# LED_SCHEMATIC.net
KiCad netlist of a schematic drawn in EasyEDA
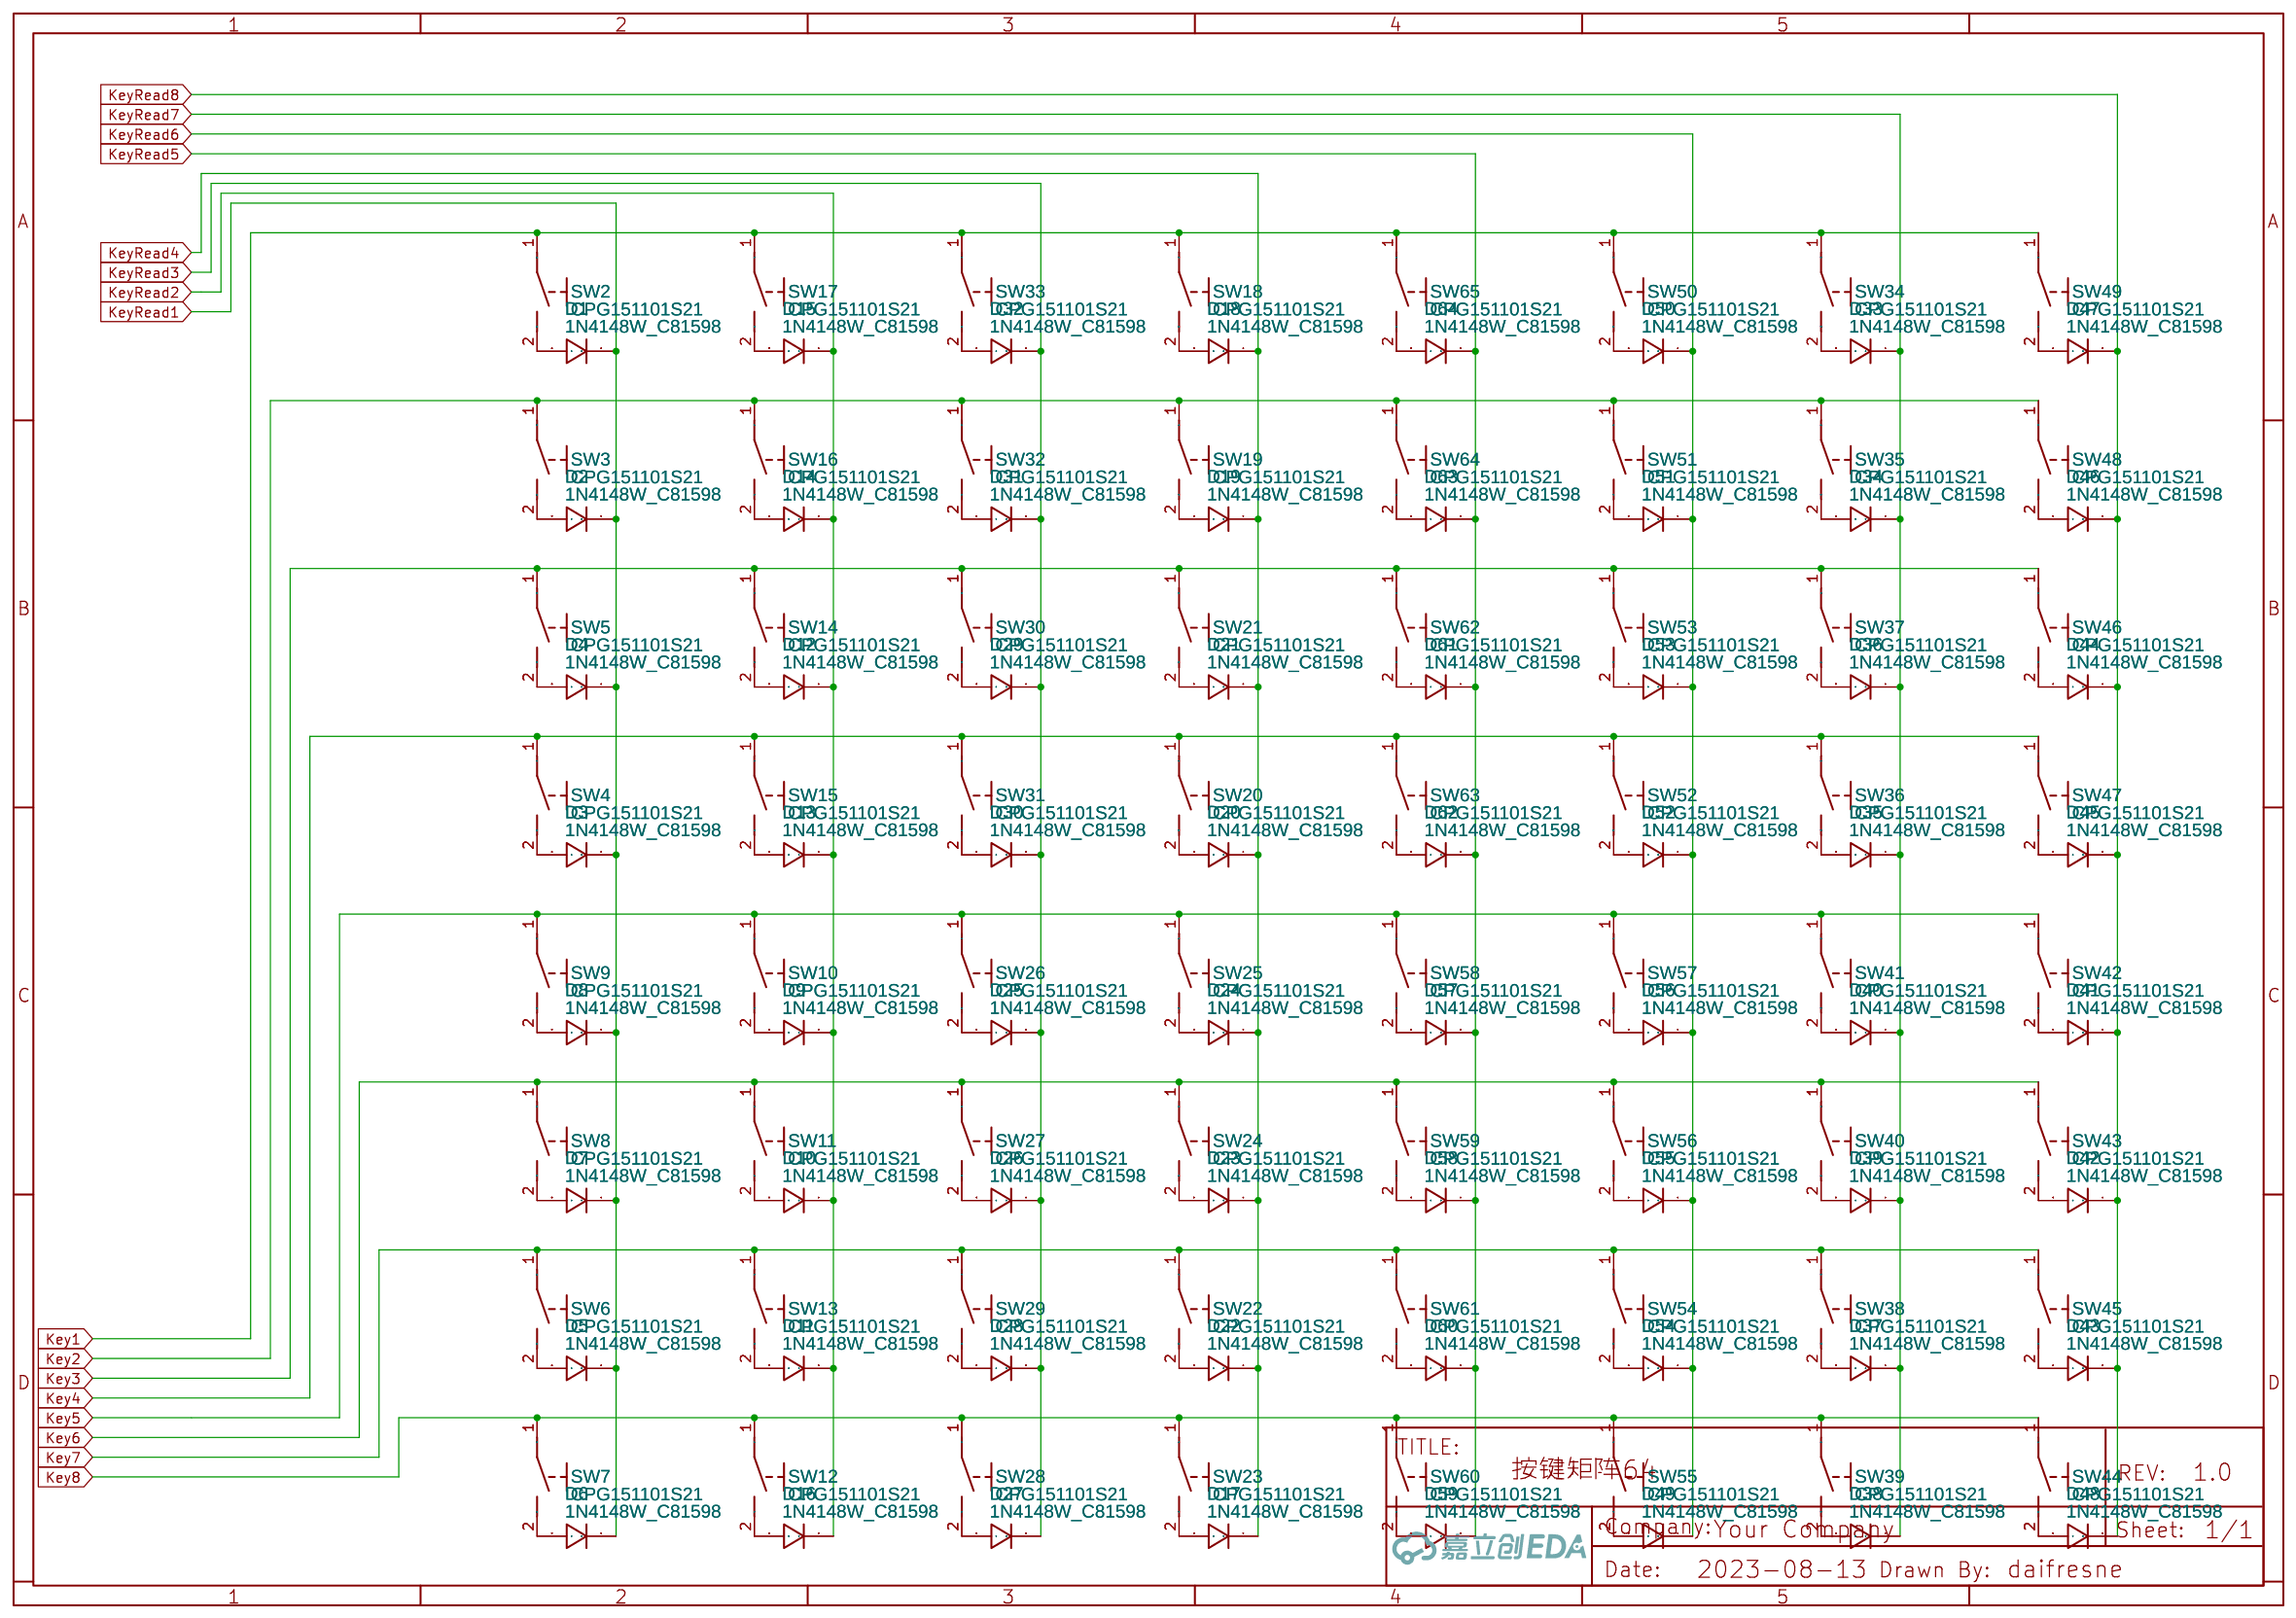
[diagram p0: 按键矩阵64]
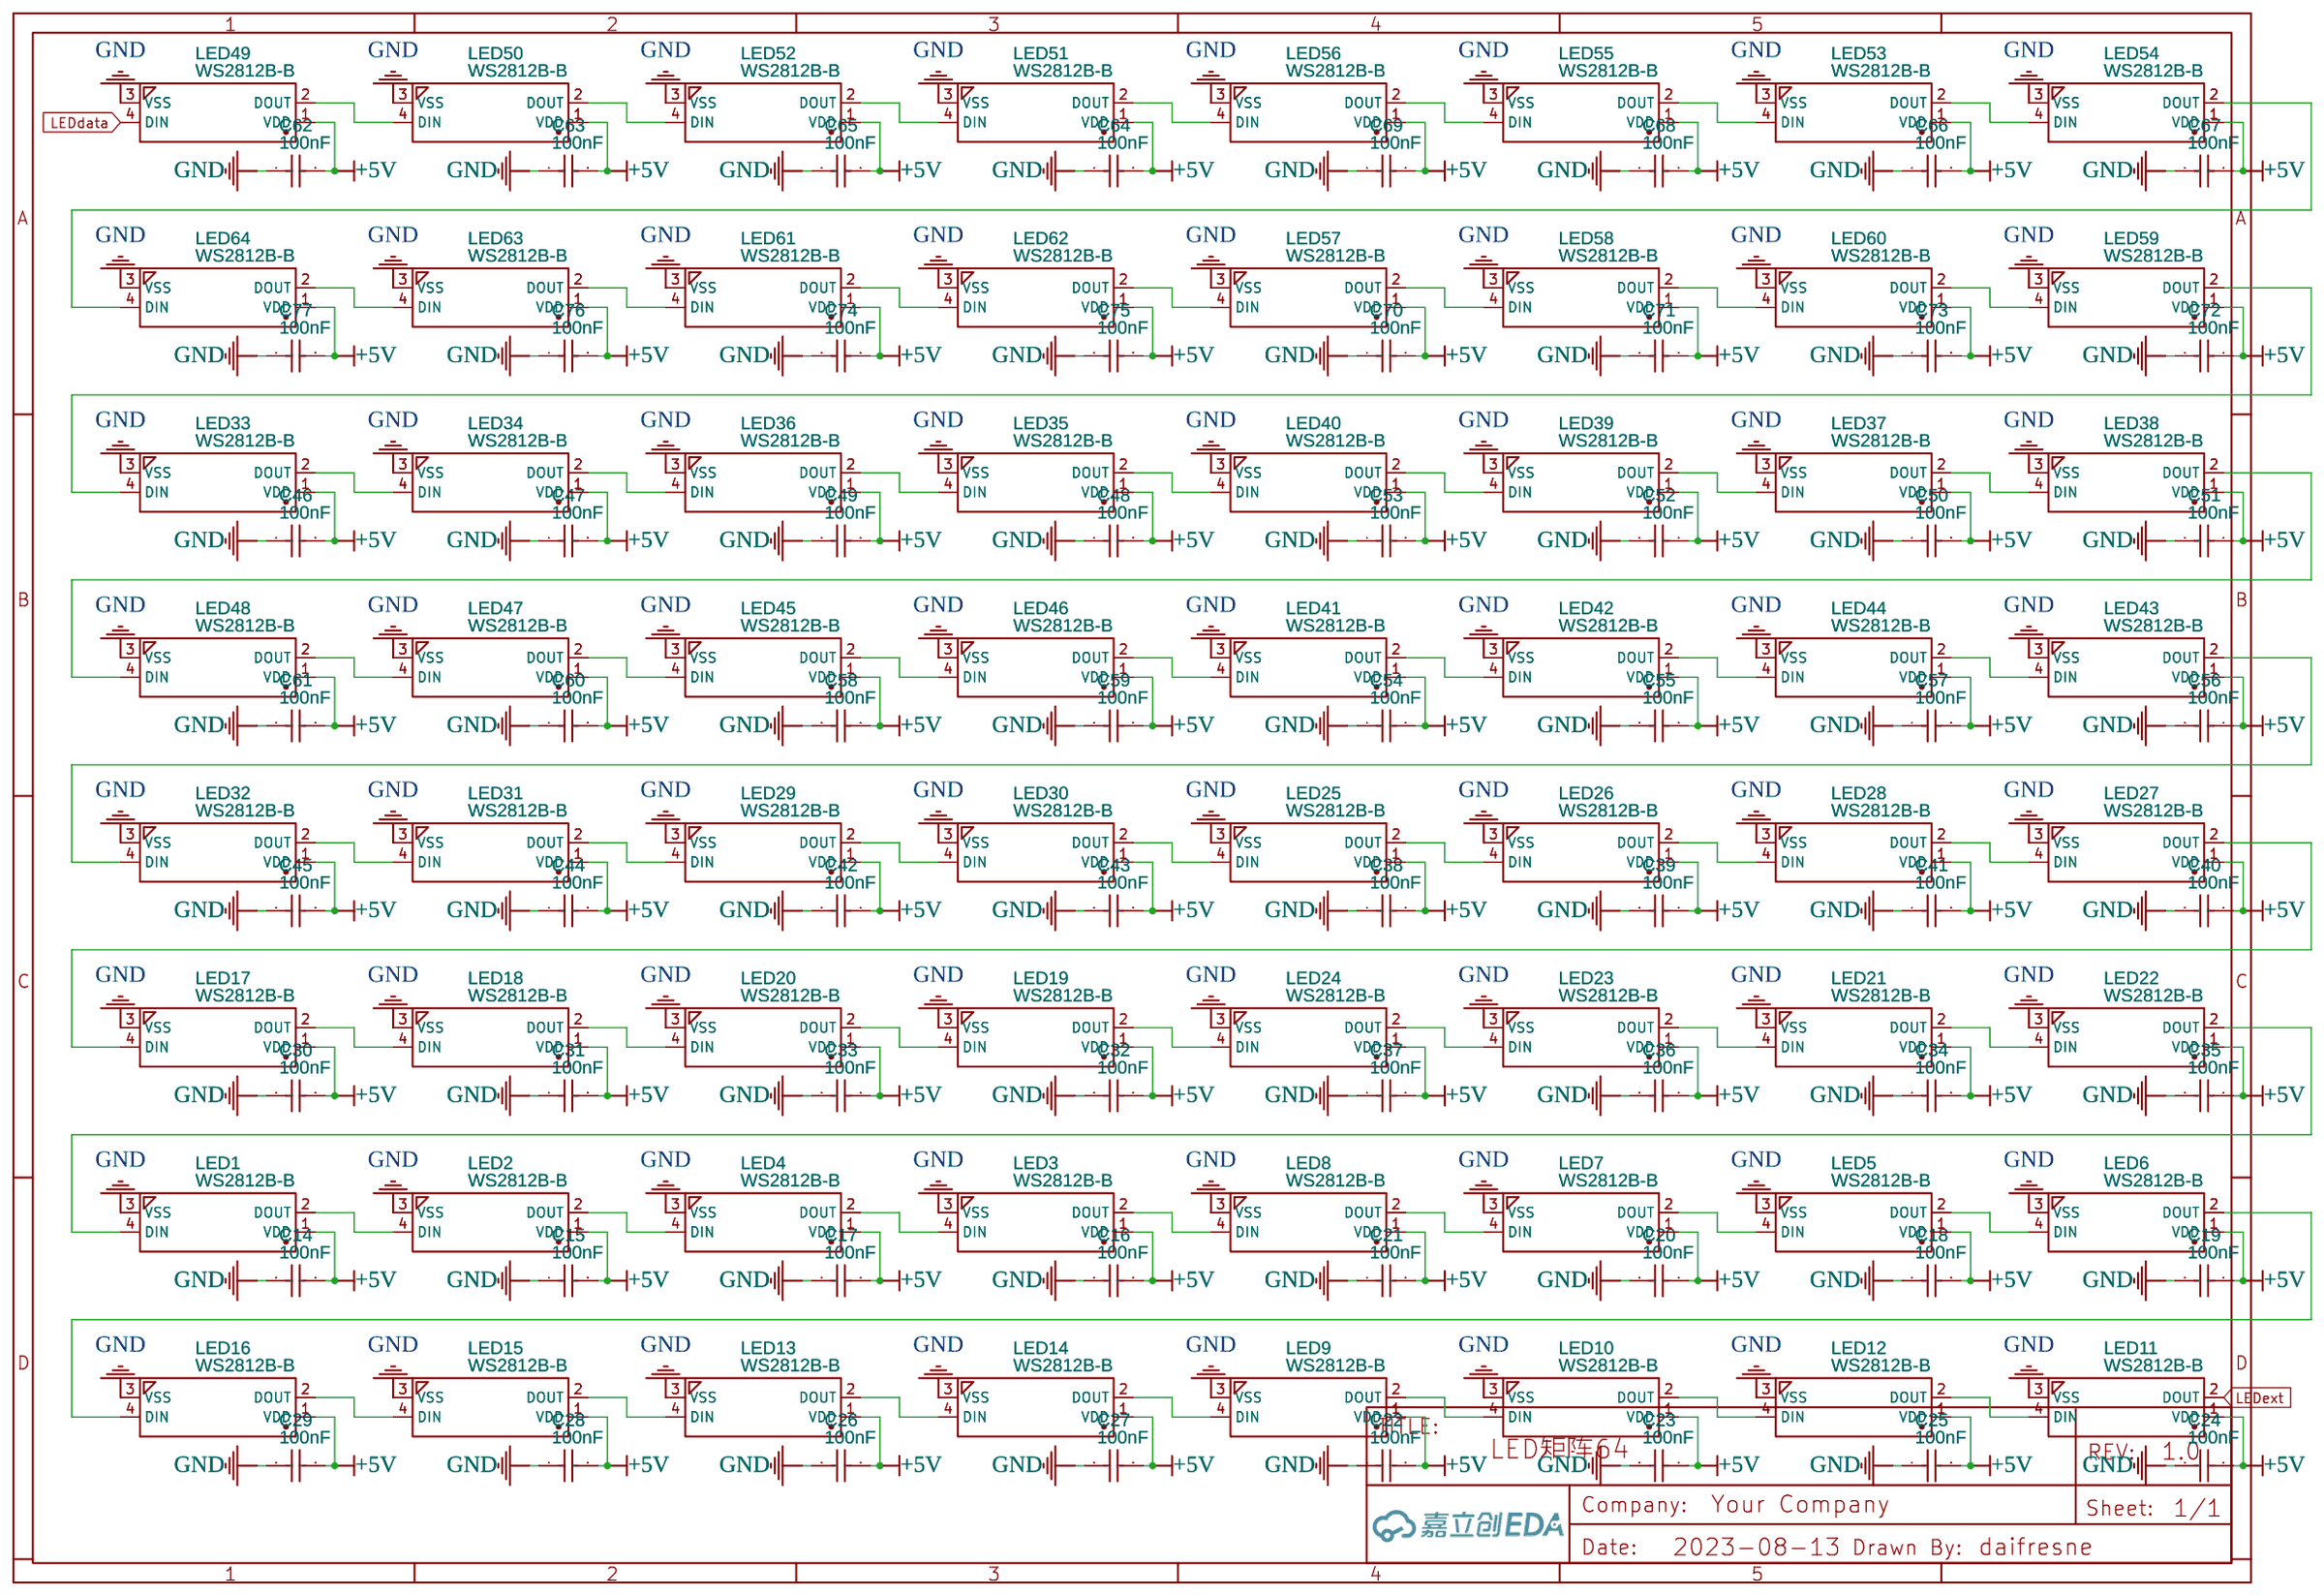
[diagram p1: LED矩阵64]

(export (version "E")
  (design (tool "Eeschema 10.0.6"))
  (components
    (comp (ref "D1")
      (value "1N4148W_C81598")
      (fields (field (name "Manufacturer") "ST(先科)"))
      (libsource (lib "") (part "1N4148W_C81598"))
    )
    (comp (ref "D2")
      (value "1N4148W_C81598")
      (fields (field (name "Manufacturer") "ST(先科)"))
      (libsource (lib "") (part "1N4148W_C81598"))
    )
    (comp (ref "D3")
      (value "1N4148W_C81598")
      (fields (field (name "Manufacturer") "ST(先科)"))
      (libsource (lib "") (part "1N4148W_C81598"))
    )
    (comp (ref "D4")
      (value "1N4148W_C81598")
      (fields (field (name "Manufacturer") "ST(先科)"))
      (libsource (lib "") (part "1N4148W_C81598"))
    )
    (comp (ref "D5")
      (value "1N4148W_C81598")
      (fields (field (name "Manufacturer") "ST(先科)"))
      (libsource (lib "") (part "1N4148W_C81598"))
    )
    (comp (ref "D6")
      (value "1N4148W_C81598")
      (fields (field (name "Manufacturer") "ST(先科)"))
      (libsource (lib "") (part "1N4148W_C81598"))
    )
    (comp (ref "D7")
      (value "1N4148W_C81598")
      (fields (field (name "Manufacturer") "ST(先科)"))
      (libsource (lib "") (part "1N4148W_C81598"))
    )
    (comp (ref "D8")
      (value "1N4148W_C81598")
      (fields (field (name "Manufacturer") "ST(先科)"))
      (libsource (lib "") (part "1N4148W_C81598"))
    )
    (comp (ref "D9")
      (value "1N4148W_C81598")
      (fields (field (name "Manufacturer") "ST(先科)"))
      (libsource (lib "") (part "1N4148W_C81598"))
    )
    (comp (ref "D10")
      (value "1N4148W_C81598")
      (fields (field (name "Manufacturer") "ST(先科)"))
      (libsource (lib "") (part "1N4148W_C81598"))
    )
    (comp (ref "D11")
      (value "1N4148W_C81598")
      (fields (field (name "Manufacturer") "ST(先科)"))
      (libsource (lib "") (part "1N4148W_C81598"))
    )
    (comp (ref "D12")
      (value "1N4148W_C81598")
      (fields (field (name "Manufacturer") "ST(先科)"))
      (libsource (lib "") (part "1N4148W_C81598"))
    )
    (comp (ref "D13")
      (value "1N4148W_C81598")
      (fields (field (name "Manufacturer") "ST(先科)"))
      (libsource (lib "") (part "1N4148W_C81598"))
    )
    (comp (ref "D14")
      (value "1N4148W_C81598")
      (fields (field (name "Manufacturer") "ST(先科)"))
      (libsource (lib "") (part "1N4148W_C81598"))
    )
    (comp (ref "D15")
      (value "1N4148W_C81598")
      (fields (field (name "Manufacturer") "ST(先科)"))
      (libsource (lib "") (part "1N4148W_C81598"))
    )
    (comp (ref "D16")
      (value "1N4148W_C81598")
      (fields (field (name "Manufacturer") "ST(先科)"))
      (libsource (lib "") (part "1N4148W_C81598"))
    )
    (comp (ref "D17")
      (value "1N4148W_C81598")
      (fields (field (name "Manufacturer") "ST(先科)"))
      (libsource (lib "") (part "1N4148W_C81598"))
    )
    (comp (ref "D18")
      (value "1N4148W_C81598")
      (fields (field (name "Manufacturer") "ST(先科)"))
      (libsource (lib "") (part "1N4148W_C81598"))
    )
    (comp (ref "D19")
      (value "1N4148W_C81598")
      (fields (field (name "Manufacturer") "ST(先科)"))
      (libsource (lib "") (part "1N4148W_C81598"))
    )
    (comp (ref "D20")
      (value "1N4148W_C81598")
      (fields (field (name "Manufacturer") "ST(先科)"))
      (libsource (lib "") (part "1N4148W_C81598"))
    )
    (comp (ref "D21")
      (value "1N4148W_C81598")
      (fields (field (name "Manufacturer") "ST(先科)"))
      (libsource (lib "") (part "1N4148W_C81598"))
    )
    (comp (ref "D22")
      (value "1N4148W_C81598")
      (fields (field (name "Manufacturer") "ST(先科)"))
      (libsource (lib "") (part "1N4148W_C81598"))
    )
    (comp (ref "D23")
      (value "1N4148W_C81598")
      (fields (field (name "Manufacturer") "ST(先科)"))
      (libsource (lib "") (part "1N4148W_C81598"))
    )
    (comp (ref "D24")
      (value "1N4148W_C81598")
      (fields (field (name "Manufacturer") "ST(先科)"))
      (libsource (lib "") (part "1N4148W_C81598"))
    )
    (comp (ref "D25")
      (value "1N4148W_C81598")
      (fields (field (name "Manufacturer") "ST(先科)"))
      (libsource (lib "") (part "1N4148W_C81598"))
    )
    (comp (ref "D26")
      (value "1N4148W_C81598")
      (fields (field (name "Manufacturer") "ST(先科)"))
      (libsource (lib "") (part "1N4148W_C81598"))
    )
    (comp (ref "D27")
      (value "1N4148W_C81598")
      (fields (field (name "Manufacturer") "ST(先科)"))
      (libsource (lib "") (part "1N4148W_C81598"))
    )
    (comp (ref "D28")
      (value "1N4148W_C81598")
      (fields (field (name "Manufacturer") "ST(先科)"))
      (libsource (lib "") (part "1N4148W_C81598"))
    )
    (comp (ref "D29")
      (value "1N4148W_C81598")
      (fields (field (name "Manufacturer") "ST(先科)"))
      (libsource (lib "") (part "1N4148W_C81598"))
    )
    (comp (ref "D30")
      (value "1N4148W_C81598")
      (fields (field (name "Manufacturer") "ST(先科)"))
      (libsource (lib "") (part "1N4148W_C81598"))
    )
    (comp (ref "D31")
      (value "1N4148W_C81598")
      (fields (field (name "Manufacturer") "ST(先科)"))
      (libsource (lib "") (part "1N4148W_C81598"))
    )
    (comp (ref "D32")
      (value "1N4148W_C81598")
      (fields (field (name "Manufacturer") "ST(先科)"))
      (libsource (lib "") (part "1N4148W_C81598"))
    )
    (comp (ref "D33")
      (value "1N4148W_C81598")
      (fields (field (name "Manufacturer") "ST(先科)"))
      (libsource (lib "") (part "1N4148W_C81598"))
    )
    (comp (ref "D34")
      (value "1N4148W_C81598")
      (fields (field (name "Manufacturer") "ST(先科)"))
      (libsource (lib "") (part "1N4148W_C81598"))
    )
    (comp (ref "D35")
      (value "1N4148W_C81598")
      (fields (field (name "Manufacturer") "ST(先科)"))
      (libsource (lib "") (part "1N4148W_C81598"))
    )
    (comp (ref "D36")
      (value "1N4148W_C81598")
      (fields (field (name "Manufacturer") "ST(先科)"))
      (libsource (lib "") (part "1N4148W_C81598"))
    )
    (comp (ref "D37")
      (value "1N4148W_C81598")
      (fields (field (name "Manufacturer") "ST(先科)"))
      (libsource (lib "") (part "1N4148W_C81598"))
    )
    (comp (ref "D38")
      (value "1N4148W_C81598")
      (fields (field (name "Manufacturer") "ST(先科)"))
      (libsource (lib "") (part "1N4148W_C81598"))
    )
    (comp (ref "D39")
      (value "1N4148W_C81598")
      (fields (field (name "Manufacturer") "ST(先科)"))
      (libsource (lib "") (part "1N4148W_C81598"))
    )
    (comp (ref "D40")
      (value "1N4148W_C81598")
      (fields (field (name "Manufacturer") "ST(先科)"))
      (libsource (lib "") (part "1N4148W_C81598"))
    )
    (comp (ref "D41")
      (value "1N4148W_C81598")
      (fields (field (name "Manufacturer") "ST(先科)"))
      (libsource (lib "") (part "1N4148W_C81598"))
    )
    (comp (ref "D42")
      (value "1N4148W_C81598")
      (fields (field (name "Manufacturer") "ST(先科)"))
      (libsource (lib "") (part "1N4148W_C81598"))
    )
    (comp (ref "D43")
      (value "1N4148W_C81598")
      (fields (field (name "Manufacturer") "ST(先科)"))
      (libsource (lib "") (part "1N4148W_C81598"))
    )
    (comp (ref "D44")
      (value "1N4148W_C81598")
      (fields (field (name "Manufacturer") "ST(先科)"))
      (libsource (lib "") (part "1N4148W_C81598"))
    )
    (comp (ref "D45")
      (value "1N4148W_C81598")
      (fields (field (name "Manufacturer") "ST(先科)"))
      (libsource (lib "") (part "1N4148W_C81598"))
    )
    (comp (ref "D46")
      (value "1N4148W_C81598")
      (fields (field (name "Manufacturer") "ST(先科)"))
      (libsource (lib "") (part "1N4148W_C81598"))
    )
    (comp (ref "D47")
      (value "1N4148W_C81598")
      (fields (field (name "Manufacturer") "ST(先科)"))
      (libsource (lib "") (part "1N4148W_C81598"))
    )
    (comp (ref "D48")
      (value "1N4148W_C81598")
      (fields (field (name "Manufacturer") "ST(先科)"))
      (libsource (lib "") (part "1N4148W_C81598"))
    )
    (comp (ref "D49")
      (value "1N4148W_C81598")
      (fields (field (name "Manufacturer") "ST(先科)"))
      (libsource (lib "") (part "1N4148W_C81598"))
    )
    (comp (ref "D50")
      (value "1N4148W_C81598")
      (fields (field (name "Manufacturer") "ST(先科)"))
      (libsource (lib "") (part "1N4148W_C81598"))
    )
    (comp (ref "D51")
      (value "1N4148W_C81598")
      (fields (field (name "Manufacturer") "ST(先科)"))
      (libsource (lib "") (part "1N4148W_C81598"))
    )
    (comp (ref "D52")
      (value "1N4148W_C81598")
      (fields (field (name "Manufacturer") "ST(先科)"))
      (libsource (lib "") (part "1N4148W_C81598"))
    )
    (comp (ref "D53")
      (value "1N4148W_C81598")
      (fields (field (name "Manufacturer") "ST(先科)"))
      (libsource (lib "") (part "1N4148W_C81598"))
    )
    (comp (ref "D54")
      (value "1N4148W_C81598")
      (fields (field (name "Manufacturer") "ST(先科)"))
      (libsource (lib "") (part "1N4148W_C81598"))
    )
    (comp (ref "D55")
      (value "1N4148W_C81598")
      (fields (field (name "Manufacturer") "ST(先科)"))
      (libsource (lib "") (part "1N4148W_C81598"))
    )
    (comp (ref "D56")
      (value "1N4148W_C81598")
      (fields (field (name "Manufacturer") "ST(先科)"))
      (libsource (lib "") (part "1N4148W_C81598"))
    )
    (comp (ref "D57")
      (value "1N4148W_C81598")
      (fields (field (name "Manufacturer") "ST(先科)"))
      (libsource (lib "") (part "1N4148W_C81598"))
    )
    (comp (ref "D58")
      (value "1N4148W_C81598")
      (fields (field (name "Manufacturer") "ST(先科)"))
      (libsource (lib "") (part "1N4148W_C81598"))
    )
    (comp (ref "D59")
      (value "1N4148W_C81598")
      (fields (field (name "Manufacturer") "ST(先科)"))
      (libsource (lib "") (part "1N4148W_C81598"))
    )
    (comp (ref "D60")
      (value "1N4148W_C81598")
      (fields (field (name "Manufacturer") "ST(先科)"))
      (libsource (lib "") (part "1N4148W_C81598"))
    )
    (comp (ref "D61")
      (value "1N4148W_C81598")
      (fields (field (name "Manufacturer") "ST(先科)"))
      (libsource (lib "") (part "1N4148W_C81598"))
    )
    (comp (ref "D62")
      (value "1N4148W_C81598")
      (fields (field (name "Manufacturer") "ST(先科)"))
      (libsource (lib "") (part "1N4148W_C81598"))
    )
    (comp (ref "D63")
      (value "1N4148W_C81598")
      (fields (field (name "Manufacturer") "ST(先科)"))
      (libsource (lib "") (part "1N4148W_C81598"))
    )
    (comp (ref "D64")
      (value "1N4148W_C81598")
      (fields (field (name "Manufacturer") "ST(先科)"))
      (libsource (lib "") (part "1N4148W_C81598"))
    )
    (comp (ref "SW2")
      (value "CPG151101S21")
      (fields (field (name "Manufacturer") "Kailh(凯华)"))
      (libsource (lib "") (part "CPG151101S21"))
    )
    (comp (ref "SW3")
      (value "CPG151101S21")
      (fields (field (name "Manufacturer") "Kailh(凯华)"))
      (libsource (lib "") (part "CPG151101S21"))
    )
    (comp (ref "SW4")
      (value "CPG151101S21")
      (fields (field (name "Manufacturer") "Kailh(凯华)"))
      (libsource (lib "") (part "CPG151101S21"))
    )
    (comp (ref "SW5")
      (value "CPG151101S21")
      (fields (field (name "Manufacturer") "Kailh(凯华)"))
      (libsource (lib "") (part "CPG151101S21"))
    )
    (comp (ref "SW6")
      (value "CPG151101S21")
      (fields (field (name "Manufacturer") "Kailh(凯华)"))
      (libsource (lib "") (part "CPG151101S21"))
    )
    (comp (ref "SW7")
      (value "CPG151101S21")
      (fields (field (name "Manufacturer") "Kailh(凯华)"))
      (libsource (lib "") (part "CPG151101S21"))
    )
    (comp (ref "SW8")
      (value "CPG151101S21")
      (fields (field (name "Manufacturer") "Kailh(凯华)"))
      (libsource (lib "") (part "CPG151101S21"))
    )
    (comp (ref "SW9")
      (value "CPG151101S21")
      (fields (field (name "Manufacturer") "Kailh(凯华)"))
      (libsource (lib "") (part "CPG151101S21"))
    )
    (comp (ref "SW10")
      (value "CPG151101S21")
      (fields (field (name "Manufacturer") "Kailh(凯华)"))
      (libsource (lib "") (part "CPG151101S21"))
    )
    (comp (ref "SW11")
      (value "CPG151101S21")
      (fields (field (name "Manufacturer") "Kailh(凯华)"))
      (libsource (lib "") (part "CPG151101S21"))
    )
    (comp (ref "SW12")
      (value "CPG151101S21")
      (fields (field (name "Manufacturer") "Kailh(凯华)"))
      (libsource (lib "") (part "CPG151101S21"))
    )
    (comp (ref "SW13")
      (value "CPG151101S21")
      (fields (field (name "Manufacturer") "Kailh(凯华)"))
      (libsource (lib "") (part "CPG151101S21"))
    )
    (comp (ref "SW14")
      (value "CPG151101S21")
      (fields (field (name "Manufacturer") "Kailh(凯华)"))
      (libsource (lib "") (part "CPG151101S21"))
    )
    (comp (ref "SW15")
      (value "CPG151101S21")
      (fields (field (name "Manufacturer") "Kailh(凯华)"))
      (libsource (lib "") (part "CPG151101S21"))
    )
    (comp (ref "SW16")
      (value "CPG151101S21")
      (fields (field (name "Manufacturer") "Kailh(凯华)"))
      (libsource (lib "") (part "CPG151101S21"))
    )
    (comp (ref "SW17")
      (value "CPG151101S21")
      (fields (field (name "Manufacturer") "Kailh(凯华)"))
      (libsource (lib "") (part "CPG151101S21"))
    )
    (comp (ref "SW18")
      (value "CPG151101S21")
      (fields (field (name "Manufacturer") "Kailh(凯华)"))
      (libsource (lib "") (part "CPG151101S21"))
    )
    (comp (ref "SW19")
      (value "CPG151101S21")
      (fields (field (name "Manufacturer") "Kailh(凯华)"))
      (libsource (lib "") (part "CPG151101S21"))
    )
    (comp (ref "SW20")
      (value "CPG151101S21")
      (fields (field (name "Manufacturer") "Kailh(凯华)"))
      (libsource (lib "") (part "CPG151101S21"))
    )
    (comp (ref "SW21")
      (value "CPG151101S21")
      (fields (field (name "Manufacturer") "Kailh(凯华)"))
      (libsource (lib "") (part "CPG151101S21"))
    )
    (comp (ref "SW22")
      (value "CPG151101S21")
      (fields (field (name "Manufacturer") "Kailh(凯华)"))
      (libsource (lib "") (part "CPG151101S21"))
    )
    (comp (ref "SW23")
      (value "CPG151101S21")
      (fields (field (name "Manufacturer") "Kailh(凯华)"))
      (libsource (lib "") (part "CPG151101S21"))
    )
    (comp (ref "SW24")
      (value "CPG151101S21")
      (fields (field (name "Manufacturer") "Kailh(凯华)"))
      (libsource (lib "") (part "CPG151101S21"))
    )
    (comp (ref "SW25")
      (value "CPG151101S21")
      (fields (field (name "Manufacturer") "Kailh(凯华)"))
      (libsource (lib "") (part "CPG151101S21"))
    )
    (comp (ref "SW26")
      (value "CPG151101S21")
      (fields (field (name "Manufacturer") "Kailh(凯华)"))
      (libsource (lib "") (part "CPG151101S21"))
    )
    (comp (ref "SW27")
      (value "CPG151101S21")
      (fields (field (name "Manufacturer") "Kailh(凯华)"))
      (libsource (lib "") (part "CPG151101S21"))
    )
    (comp (ref "SW28")
      (value "CPG151101S21")
      (fields (field (name "Manufacturer") "Kailh(凯华)"))
      (libsource (lib "") (part "CPG151101S21"))
    )
    (comp (ref "SW29")
      (value "CPG151101S21")
      (fields (field (name "Manufacturer") "Kailh(凯华)"))
      (libsource (lib "") (part "CPG151101S21"))
    )
    (comp (ref "SW30")
      (value "CPG151101S21")
      (fields (field (name "Manufacturer") "Kailh(凯华)"))
      (libsource (lib "") (part "CPG151101S21"))
    )
    (comp (ref "SW31")
      (value "CPG151101S21")
      (fields (field (name "Manufacturer") "Kailh(凯华)"))
      (libsource (lib "") (part "CPG151101S21"))
    )
    (comp (ref "SW32")
      (value "CPG151101S21")
      (fields (field (name "Manufacturer") "Kailh(凯华)"))
      (libsource (lib "") (part "CPG151101S21"))
    )
    (comp (ref "SW33")
      (value "CPG151101S21")
      (fields (field (name "Manufacturer") "Kailh(凯华)"))
      (libsource (lib "") (part "CPG151101S21"))
    )
    (comp (ref "SW34")
      (value "CPG151101S21")
      (fields (field (name "Manufacturer") "Kailh(凯华)"))
      (libsource (lib "") (part "CPG151101S21"))
    )
    (comp (ref "SW35")
      (value "CPG151101S21")
      (fields (field (name "Manufacturer") "Kailh(凯华)"))
      (libsource (lib "") (part "CPG151101S21"))
    )
    (comp (ref "SW36")
      (value "CPG151101S21")
      (fields (field (name "Manufacturer") "Kailh(凯华)"))
      (libsource (lib "") (part "CPG151101S21"))
    )
    (comp (ref "SW37")
      (value "CPG151101S21")
      (fields (field (name "Manufacturer") "Kailh(凯华)"))
      (libsource (lib "") (part "CPG151101S21"))
    )
    (comp (ref "SW38")
      (value "CPG151101S21")
      (fields (field (name "Manufacturer") "Kailh(凯华)"))
      (libsource (lib "") (part "CPG151101S21"))
    )
    (comp (ref "SW39")
      (value "CPG151101S21")
      (fields (field (name "Manufacturer") "Kailh(凯华)"))
      (libsource (lib "") (part "CPG151101S21"))
    )
    (comp (ref "SW40")
      (value "CPG151101S21")
      (fields (field (name "Manufacturer") "Kailh(凯华)"))
      (libsource (lib "") (part "CPG151101S21"))
    )
    (comp (ref "SW41")
      (value "CPG151101S21")
      (fields (field (name "Manufacturer") "Kailh(凯华)"))
      (libsource (lib "") (part "CPG151101S21"))
    )
    (comp (ref "SW42")
      (value "CPG151101S21")
      (fields (field (name "Manufacturer") "Kailh(凯华)"))
      (libsource (lib "") (part "CPG151101S21"))
    )
    (comp (ref "SW43")
      (value "CPG151101S21")
      (fields (field (name "Manufacturer") "Kailh(凯华)"))
      (libsource (lib "") (part "CPG151101S21"))
    )
    (comp (ref "SW44")
      (value "CPG151101S21")
      (fields (field (name "Manufacturer") "Kailh(凯华)"))
      (libsource (lib "") (part "CPG151101S21"))
    )
    (comp (ref "SW45")
      (value "CPG151101S21")
      (fields (field (name "Manufacturer") "Kailh(凯华)"))
      (libsource (lib "") (part "CPG151101S21"))
    )
    (comp (ref "SW46")
      (value "CPG151101S21")
      (fields (field (name "Manufacturer") "Kailh(凯华)"))
      (libsource (lib "") (part "CPG151101S21"))
    )
    (comp (ref "SW47")
      (value "CPG151101S21")
      (fields (field (name "Manufacturer") "Kailh(凯华)"))
      (libsource (lib "") (part "CPG151101S21"))
    )
    (comp (ref "SW48")
      (value "CPG151101S21")
      (fields (field (name "Manufacturer") "Kailh(凯华)"))
      (libsource (lib "") (part "CPG151101S21"))
    )
    (comp (ref "SW49")
      (value "CPG151101S21")
      (fields (field (name "Manufacturer") "Kailh(凯华)"))
      (libsource (lib "") (part "CPG151101S21"))
    )
    (comp (ref "SW50")
      (value "CPG151101S21")
      (fields (field (name "Manufacturer") "Kailh(凯华)"))
      (libsource (lib "") (part "CPG151101S21"))
    )
    (comp (ref "SW51")
      (value "CPG151101S21")
      (fields (field (name "Manufacturer") "Kailh(凯华)"))
      (libsource (lib "") (part "CPG151101S21"))
    )
    (comp (ref "SW52")
      (value "CPG151101S21")
      (fields (field (name "Manufacturer") "Kailh(凯华)"))
      (libsource (lib "") (part "CPG151101S21"))
    )
    (comp (ref "SW53")
      (value "CPG151101S21")
      (fields (field (name "Manufacturer") "Kailh(凯华)"))
      (libsource (lib "") (part "CPG151101S21"))
    )
    (comp (ref "SW54")
      (value "CPG151101S21")
      (fields (field (name "Manufacturer") "Kailh(凯华)"))
      (libsource (lib "") (part "CPG151101S21"))
    )
    (comp (ref "SW55")
      (value "CPG151101S21")
      (fields (field (name "Manufacturer") "Kailh(凯华)"))
      (libsource (lib "") (part "CPG151101S21"))
    )
    (comp (ref "SW56")
      (value "CPG151101S21")
      (fields (field (name "Manufacturer") "Kailh(凯华)"))
      (libsource (lib "") (part "CPG151101S21"))
    )
    (comp (ref "SW57")
      (value "CPG151101S21")
      (fields (field (name "Manufacturer") "Kailh(凯华)"))
      (libsource (lib "") (part "CPG151101S21"))
    )
    (comp (ref "SW58")
      (value "CPG151101S21")
      (fields (field (name "Manufacturer") "Kailh(凯华)"))
      (libsource (lib "") (part "CPG151101S21"))
    )
    (comp (ref "SW59")
      (value "CPG151101S21")
      (fields (field (name "Manufacturer") "Kailh(凯华)"))
      (libsource (lib "") (part "CPG151101S21"))
    )
    (comp (ref "SW60")
      (value "CPG151101S21")
      (fields (field (name "Manufacturer") "Kailh(凯华)"))
      (libsource (lib "") (part "CPG151101S21"))
    )
    (comp (ref "SW61")
      (value "CPG151101S21")
      (fields (field (name "Manufacturer") "Kailh(凯华)"))
      (libsource (lib "") (part "CPG151101S21"))
    )
    (comp (ref "SW62")
      (value "CPG151101S21")
      (fields (field (name "Manufacturer") "Kailh(凯华)"))
      (libsource (lib "") (part "CPG151101S21"))
    )
    (comp (ref "SW63")
      (value "CPG151101S21")
      (fields (field (name "Manufacturer") "Kailh(凯华)"))
      (libsource (lib "") (part "CPG151101S21"))
    )
    (comp (ref "SW64")
      (value "CPG151101S21")
      (fields (field (name "Manufacturer") "Kailh(凯华)"))
      (libsource (lib "") (part "CPG151101S21"))
    )
    (comp (ref "SW65")
      (value "CPG151101S21")
      (fields (field (name "Manufacturer") "Kailh(凯华)"))
      (libsource (lib "") (part "CPG151101S21"))
    )
    (comp (ref "C14")
      (value "100nF")
      (fields (field (name "Manufacturer") "YAGEO(国巨)"))
      (libsource (lib "") (part "CC0603KRX7R8BB104"))
    )
    (comp (ref "C15")
      (value "100nF")
      (fields (field (name "Manufacturer") "YAGEO(国巨)"))
      (libsource (lib "") (part "CC0603KRX7R8BB104"))
    )
    (comp (ref "C16")
      (value "100nF")
      (fields (field (name "Manufacturer") "YAGEO(国巨)"))
      (libsource (lib "") (part "CC0603KRX7R8BB104"))
    )
    (comp (ref "C17")
      (value "100nF")
      (fields (field (name "Manufacturer") "YAGEO(国巨)"))
      (libsource (lib "") (part "CC0603KRX7R8BB104"))
    )
    (comp (ref "C18")
      (value "100nF")
      (fields (field (name "Manufacturer") "YAGEO(国巨)"))
      (libsource (lib "") (part "CC0603KRX7R8BB104"))
    )
    (comp (ref "C19")
      (value "100nF")
      (fields (field (name "Manufacturer") "YAGEO(国巨)"))
      (libsource (lib "") (part "CC0603KRX7R8BB104"))
    )
    (comp (ref "C20")
      (value "100nF")
      (fields (field (name "Manufacturer") "YAGEO(国巨)"))
      (libsource (lib "") (part "CC0603KRX7R8BB104"))
    )
    (comp (ref "C21")
      (value "100nF")
      (fields (field (name "Manufacturer") "YAGEO(国巨)"))
      (libsource (lib "") (part "CC0603KRX7R8BB104"))
    )
    (comp (ref "C22")
      (value "100nF")
      (fields (field (name "Manufacturer") "YAGEO(国巨)"))
      (libsource (lib "") (part "CC0603KRX7R8BB104"))
    )
    (comp (ref "C23")
      (value "100nF")
      (fields (field (name "Manufacturer") "YAGEO(国巨)"))
      (libsource (lib "") (part "CC0603KRX7R8BB104"))
    )
    (comp (ref "C24")
      (value "100nF")
      (fields (field (name "Manufacturer") "YAGEO(国巨)"))
      (libsource (lib "") (part "CC0603KRX7R8BB104"))
    )
    (comp (ref "C25")
      (value "100nF")
      (fields (field (name "Manufacturer") "YAGEO(国巨)"))
      (libsource (lib "") (part "CC0603KRX7R8BB104"))
    )
    (comp (ref "C26")
      (value "100nF")
      (fields (field (name "Manufacturer") "YAGEO(国巨)"))
      (libsource (lib "") (part "CC0603KRX7R8BB104"))
    )
    (comp (ref "C27")
      (value "100nF")
      (fields (field (name "Manufacturer") "YAGEO(国巨)"))
      (libsource (lib "") (part "CC0603KRX7R8BB104"))
    )
    (comp (ref "C28")
      (value "100nF")
      (fields (field (name "Manufacturer") "YAGEO(国巨)"))
      (libsource (lib "") (part "CC0603KRX7R8BB104"))
    )
    (comp (ref "C29")
      (value "100nF")
      (fields (field (name "Manufacturer") "YAGEO(国巨)"))
      (libsource (lib "") (part "CC0603KRX7R8BB104"))
    )
    (comp (ref "C30")
      (value "100nF")
      (fields (field (name "Manufacturer") "YAGEO(国巨)"))
      (libsource (lib "") (part "CC0603KRX7R8BB104"))
    )
    (comp (ref "C31")
      (value "100nF")
      (fields (field (name "Manufacturer") "YAGEO(国巨)"))
      (libsource (lib "") (part "CC0603KRX7R8BB104"))
    )
    (comp (ref "C32")
      (value "100nF")
      (fields (field (name "Manufacturer") "YAGEO(国巨)"))
      (libsource (lib "") (part "CC0603KRX7R8BB104"))
    )
    (comp (ref "C33")
      (value "100nF")
      (fields (field (name "Manufacturer") "YAGEO(国巨)"))
      (libsource (lib "") (part "CC0603KRX7R8BB104"))
    )
    (comp (ref "C34")
      (value "100nF")
      (fields (field (name "Manufacturer") "YAGEO(国巨)"))
      (libsource (lib "") (part "CC0603KRX7R8BB104"))
    )
    (comp (ref "C35")
      (value "100nF")
      (fields (field (name "Manufacturer") "YAGEO(国巨)"))
      (libsource (lib "") (part "CC0603KRX7R8BB104"))
    )
    (comp (ref "C36")
      (value "100nF")
      (fields (field (name "Manufacturer") "YAGEO(国巨)"))
      (libsource (lib "") (part "CC0603KRX7R8BB104"))
    )
    (comp (ref "C37")
      (value "100nF")
      (fields (field (name "Manufacturer") "YAGEO(国巨)"))
      (libsource (lib "") (part "CC0603KRX7R8BB104"))
    )
    (comp (ref "C38")
      (value "100nF")
      (fields (field (name "Manufacturer") "YAGEO(国巨)"))
      (libsource (lib "") (part "CC0603KRX7R8BB104"))
    )
    (comp (ref "C39")
      (value "100nF")
      (fields (field (name "Manufacturer") "YAGEO(国巨)"))
      (libsource (lib "") (part "CC0603KRX7R8BB104"))
    )
    (comp (ref "C40")
      (value "100nF")
      (fields (field (name "Manufacturer") "YAGEO(国巨)"))
      (libsource (lib "") (part "CC0603KRX7R8BB104"))
    )
    (comp (ref "C41")
      (value "100nF")
      (fields (field (name "Manufacturer") "YAGEO(国巨)"))
      (libsource (lib "") (part "CC0603KRX7R8BB104"))
    )
    (comp (ref "C42")
      (value "100nF")
      (fields (field (name "Manufacturer") "YAGEO(国巨)"))
      (libsource (lib "") (part "CC0603KRX7R8BB104"))
    )
    (comp (ref "C43")
      (value "100nF")
      (fields (field (name "Manufacturer") "YAGEO(国巨)"))
      (libsource (lib "") (part "CC0603KRX7R8BB104"))
    )
    (comp (ref "C44")
      (value "100nF")
      (fields (field (name "Manufacturer") "YAGEO(国巨)"))
      (libsource (lib "") (part "CC0603KRX7R8BB104"))
    )
    (comp (ref "C45")
      (value "100nF")
      (fields (field (name "Manufacturer") "YAGEO(国巨)"))
      (libsource (lib "") (part "CC0603KRX7R8BB104"))
    )
    (comp (ref "C46")
      (value "100nF")
      (fields (field (name "Manufacturer") "YAGEO(国巨)"))
      (libsource (lib "") (part "CC0603KRX7R8BB104"))
    )
    (comp (ref "C47")
      (value "100nF")
      (fields (field (name "Manufacturer") "YAGEO(国巨)"))
      (libsource (lib "") (part "CC0603KRX7R8BB104"))
    )
    (comp (ref "C48")
      (value "100nF")
      (fields (field (name "Manufacturer") "YAGEO(国巨)"))
      (libsource (lib "") (part "CC0603KRX7R8BB104"))
    )
    (comp (ref "C49")
      (value "100nF")
      (fields (field (name "Manufacturer") "YAGEO(国巨)"))
      (libsource (lib "") (part "CC0603KRX7R8BB104"))
    )
    (comp (ref "C50")
      (value "100nF")
      (fields (field (name "Manufacturer") "YAGEO(国巨)"))
      (libsource (lib "") (part "CC0603KRX7R8BB104"))
    )
    (comp (ref "C51")
      (value "100nF")
      (fields (field (name "Manufacturer") "YAGEO(国巨)"))
      (libsource (lib "") (part "CC0603KRX7R8BB104"))
    )
    (comp (ref "C52")
      (value "100nF")
      (fields (field (name "Manufacturer") "YAGEO(国巨)"))
      (libsource (lib "") (part "CC0603KRX7R8BB104"))
    )
    (comp (ref "C53")
      (value "100nF")
      (fields (field (name "Manufacturer") "YAGEO(国巨)"))
      (libsource (lib "") (part "CC0603KRX7R8BB104"))
    )
    (comp (ref "C54")
      (value "100nF")
      (fields (field (name "Manufacturer") "YAGEO(国巨)"))
      (libsource (lib "") (part "CC0603KRX7R8BB104"))
    )
    (comp (ref "C55")
      (value "100nF")
      (fields (field (name "Manufacturer") "YAGEO(国巨)"))
      (libsource (lib "") (part "CC0603KRX7R8BB104"))
    )
    (comp (ref "C56")
      (value "100nF")
      (fields (field (name "Manufacturer") "YAGEO(国巨)"))
      (libsource (lib "") (part "CC0603KRX7R8BB104"))
    )
    (comp (ref "C57")
      (value "100nF")
      (fields (field (name "Manufacturer") "YAGEO(国巨)"))
      (libsource (lib "") (part "CC0603KRX7R8BB104"))
    )
    (comp (ref "C58")
      (value "100nF")
      (fields (field (name "Manufacturer") "YAGEO(国巨)"))
      (libsource (lib "") (part "CC0603KRX7R8BB104"))
    )
    (comp (ref "C59")
      (value "100nF")
      (fields (field (name "Manufacturer") "YAGEO(国巨)"))
      (libsource (lib "") (part "CC0603KRX7R8BB104"))
    )
    (comp (ref "C60")
      (value "100nF")
      (fields (field (name "Manufacturer") "YAGEO(国巨)"))
      (libsource (lib "") (part "CC0603KRX7R8BB104"))
    )
    (comp (ref "C61")
      (value "100nF")
      (fields (field (name "Manufacturer") "YAGEO(国巨)"))
      (libsource (lib "") (part "CC0603KRX7R8BB104"))
    )
    (comp (ref "C62")
      (value "100nF")
      (fields (field (name "Manufacturer") "YAGEO(国巨)"))
      (libsource (lib "") (part "CC0603KRX7R8BB104"))
    )
    (comp (ref "C63")
      (value "100nF")
      (fields (field (name "Manufacturer") "YAGEO(国巨)"))
      (libsource (lib "") (part "CC0603KRX7R8BB104"))
    )
    (comp (ref "C64")
      (value "100nF")
      (fields (field (name "Manufacturer") "YAGEO(国巨)"))
      (libsource (lib "") (part "CC0603KRX7R8BB104"))
    )
    (comp (ref "C65")
      (value "100nF")
      (fields (field (name "Manufacturer") "YAGEO(国巨)"))
      (libsource (lib "") (part "CC0603KRX7R8BB104"))
    )
    (comp (ref "C66")
      (value "100nF")
      (fields (field (name "Manufacturer") "YAGEO(国巨)"))
      (libsource (lib "") (part "CC0603KRX7R8BB104"))
    )
    (comp (ref "C67")
      (value "100nF")
      (fields (field (name "Manufacturer") "YAGEO(国巨)"))
      (libsource (lib "") (part "CC0603KRX7R8BB104"))
    )
    (comp (ref "C68")
      (value "100nF")
      (fields (field (name "Manufacturer") "YAGEO(国巨)"))
      (libsource (lib "") (part "CC0603KRX7R8BB104"))
    )
    (comp (ref "C69")
      (value "100nF")
      (fields (field (name "Manufacturer") "YAGEO(国巨)"))
      (libsource (lib "") (part "CC0603KRX7R8BB104"))
    )
    (comp (ref "C70")
      (value "100nF")
      (fields (field (name "Manufacturer") "YAGEO(国巨)"))
      (libsource (lib "") (part "CC0603KRX7R8BB104"))
    )
    (comp (ref "C71")
      (value "100nF")
      (fields (field (name "Manufacturer") "YAGEO(国巨)"))
      (libsource (lib "") (part "CC0603KRX7R8BB104"))
    )
    (comp (ref "C72")
      (value "100nF")
      (fields (field (name "Manufacturer") "YAGEO(国巨)"))
      (libsource (lib "") (part "CC0603KRX7R8BB104"))
    )
    (comp (ref "C73")
      (value "100nF")
      (fields (field (name "Manufacturer") "YAGEO(国巨)"))
      (libsource (lib "") (part "CC0603KRX7R8BB104"))
    )
    (comp (ref "C74")
      (value "100nF")
      (fields (field (name "Manufacturer") "YAGEO(国巨)"))
      (libsource (lib "") (part "CC0603KRX7R8BB104"))
    )
    (comp (ref "C75")
      (value "100nF")
      (fields (field (name "Manufacturer") "YAGEO(国巨)"))
      (libsource (lib "") (part "CC0603KRX7R8BB104"))
    )
    (comp (ref "C76")
      (value "100nF")
      (fields (field (name "Manufacturer") "YAGEO(国巨)"))
      (libsource (lib "") (part "CC0603KRX7R8BB104"))
    )
    (comp (ref "C77")
      (value "100nF")
      (fields (field (name "Manufacturer") "YAGEO(国巨)"))
      (libsource (lib "") (part "CC0603KRX7R8BB104"))
    )
    (comp (ref "LED1")
      (value "WS2812B-B")
      (fields (field (name "Manufacturer") "worldsemi"))
      (libsource (lib "") (part "WS2812B-B"))
    )
    (comp (ref "LED2")
      (value "WS2812B-B")
      (fields (field (name "Manufacturer") "worldsemi"))
      (libsource (lib "") (part "WS2812B-B"))
    )
    (comp (ref "LED3")
      (value "WS2812B-B")
      (fields (field (name "Manufacturer") "worldsemi"))
      (libsource (lib "") (part "WS2812B-B"))
    )
    (comp (ref "LED4")
      (value "WS2812B-B")
      (fields (field (name "Manufacturer") "worldsemi"))
      (libsource (lib "") (part "WS2812B-B"))
    )
    (comp (ref "LED5")
      (value "WS2812B-B")
      (fields (field (name "Manufacturer") "worldsemi"))
      (libsource (lib "") (part "WS2812B-B"))
    )
    (comp (ref "LED6")
      (value "WS2812B-B")
      (fields (field (name "Manufacturer") "worldsemi"))
      (libsource (lib "") (part "WS2812B-B"))
    )
    (comp (ref "LED7")
      (value "WS2812B-B")
      (fields (field (name "Manufacturer") "worldsemi"))
      (libsource (lib "") (part "WS2812B-B"))
    )
    (comp (ref "LED8")
      (value "WS2812B-B")
      (fields (field (name "Manufacturer") "worldsemi"))
      (libsource (lib "") (part "WS2812B-B"))
    )
    (comp (ref "LED9")
      (value "WS2812B-B")
      (fields (field (name "Manufacturer") "worldsemi"))
      (libsource (lib "") (part "WS2812B-B"))
    )
    (comp (ref "LED10")
      (value "WS2812B-B")
      (fields (field (name "Manufacturer") "worldsemi"))
      (libsource (lib "") (part "WS2812B-B"))
    )
    (comp (ref "LED11")
      (value "WS2812B-B")
      (fields (field (name "Manufacturer") "worldsemi"))
      (libsource (lib "") (part "WS2812B-B"))
    )
    (comp (ref "LED12")
      (value "WS2812B-B")
      (fields (field (name "Manufacturer") "worldsemi"))
      (libsource (lib "") (part "WS2812B-B"))
    )
    (comp (ref "LED13")
      (value "WS2812B-B")
      (fields (field (name "Manufacturer") "worldsemi"))
      (libsource (lib "") (part "WS2812B-B"))
    )
    (comp (ref "LED14")
      (value "WS2812B-B")
      (fields (field (name "Manufacturer") "worldsemi"))
      (libsource (lib "") (part "WS2812B-B"))
    )
    (comp (ref "LED15")
      (value "WS2812B-B")
      (fields (field (name "Manufacturer") "worldsemi"))
      (libsource (lib "") (part "WS2812B-B"))
    )
    (comp (ref "LED16")
      (value "WS2812B-B")
      (fields (field (name "Manufacturer") "worldsemi"))
      (libsource (lib "") (part "WS2812B-B"))
    )
    (comp (ref "LED17")
      (value "WS2812B-B")
      (fields (field (name "Manufacturer") "worldsemi"))
      (libsource (lib "") (part "WS2812B-B"))
    )
    (comp (ref "LED18")
      (value "WS2812B-B")
      (fields (field (name "Manufacturer") "worldsemi"))
      (libsource (lib "") (part "WS2812B-B"))
    )
    (comp (ref "LED19")
      (value "WS2812B-B")
      (fields (field (name "Manufacturer") "worldsemi"))
      (libsource (lib "") (part "WS2812B-B"))
    )
    (comp (ref "LED20")
      (value "WS2812B-B")
      (fields (field (name "Manufacturer") "worldsemi"))
      (libsource (lib "") (part "WS2812B-B"))
    )
    (comp (ref "LED21")
      (value "WS2812B-B")
      (fields (field (name "Manufacturer") "worldsemi"))
      (libsource (lib "") (part "WS2812B-B"))
    )
    (comp (ref "LED22")
      (value "WS2812B-B")
      (fields (field (name "Manufacturer") "worldsemi"))
      (libsource (lib "") (part "WS2812B-B"))
    )
    (comp (ref "LED23")
      (value "WS2812B-B")
      (fields (field (name "Manufacturer") "worldsemi"))
      (libsource (lib "") (part "WS2812B-B"))
    )
    (comp (ref "LED24")
      (value "WS2812B-B")
      (fields (field (name "Manufacturer") "worldsemi"))
      (libsource (lib "") (part "WS2812B-B"))
    )
    (comp (ref "LED25")
      (value "WS2812B-B")
      (fields (field (name "Manufacturer") "worldsemi"))
      (libsource (lib "") (part "WS2812B-B"))
    )
    (comp (ref "LED26")
      (value "WS2812B-B")
      (fields (field (name "Manufacturer") "worldsemi"))
      (libsource (lib "") (part "WS2812B-B"))
    )
    (comp (ref "LED27")
      (value "WS2812B-B")
      (fields (field (name "Manufacturer") "worldsemi"))
      (libsource (lib "") (part "WS2812B-B"))
    )
    (comp (ref "LED28")
      (value "WS2812B-B")
      (fields (field (name "Manufacturer") "worldsemi"))
      (libsource (lib "") (part "WS2812B-B"))
    )
    (comp (ref "LED29")
      (value "WS2812B-B")
      (fields (field (name "Manufacturer") "worldsemi"))
      (libsource (lib "") (part "WS2812B-B"))
    )
    (comp (ref "LED30")
      (value "WS2812B-B")
      (fields (field (name "Manufacturer") "worldsemi"))
      (libsource (lib "") (part "WS2812B-B"))
    )
    (comp (ref "LED31")
      (value "WS2812B-B")
      (fields (field (name "Manufacturer") "worldsemi"))
      (libsource (lib "") (part "WS2812B-B"))
    )
    (comp (ref "LED32")
      (value "WS2812B-B")
      (fields (field (name "Manufacturer") "worldsemi"))
      (libsource (lib "") (part "WS2812B-B"))
    )
    (comp (ref "LED33")
      (value "WS2812B-B")
      (fields (field (name "Manufacturer") "worldsemi"))
      (libsource (lib "") (part "WS2812B-B"))
    )
    (comp (ref "LED34")
      (value "WS2812B-B")
      (fields (field (name "Manufacturer") "worldsemi"))
      (libsource (lib "") (part "WS2812B-B"))
    )
    (comp (ref "LED35")
      (value "WS2812B-B")
      (fields (field (name "Manufacturer") "worldsemi"))
      (libsource (lib "") (part "WS2812B-B"))
    )
    (comp (ref "LED36")
      (value "WS2812B-B")
      (fields (field (name "Manufacturer") "worldsemi"))
      (libsource (lib "") (part "WS2812B-B"))
    )
    (comp (ref "LED37")
      (value "WS2812B-B")
      (fields (field (name "Manufacturer") "worldsemi"))
      (libsource (lib "") (part "WS2812B-B"))
    )
    (comp (ref "LED38")
      (value "WS2812B-B")
      (fields (field (name "Manufacturer") "worldsemi"))
      (libsource (lib "") (part "WS2812B-B"))
    )
    (comp (ref "LED39")
      (value "WS2812B-B")
      (fields (field (name "Manufacturer") "worldsemi"))
      (libsource (lib "") (part "WS2812B-B"))
    )
    (comp (ref "LED40")
      (value "WS2812B-B")
      (fields (field (name "Manufacturer") "worldsemi"))
      (libsource (lib "") (part "WS2812B-B"))
    )
    (comp (ref "LED41")
      (value "WS2812B-B")
      (fields (field (name "Manufacturer") "worldsemi"))
      (libsource (lib "") (part "WS2812B-B"))
    )
    (comp (ref "LED42")
      (value "WS2812B-B")
      (fields (field (name "Manufacturer") "worldsemi"))
      (libsource (lib "") (part "WS2812B-B"))
    )
    (comp (ref "LED43")
      (value "WS2812B-B")
      (fields (field (name "Manufacturer") "worldsemi"))
      (libsource (lib "") (part "WS2812B-B"))
    )
    (comp (ref "LED44")
      (value "WS2812B-B")
      (fields (field (name "Manufacturer") "worldsemi"))
      (libsource (lib "") (part "WS2812B-B"))
    )
    (comp (ref "LED45")
      (value "WS2812B-B")
      (fields (field (name "Manufacturer") "worldsemi"))
      (libsource (lib "") (part "WS2812B-B"))
    )
    (comp (ref "LED46")
      (value "WS2812B-B")
      (fields (field (name "Manufacturer") "worldsemi"))
      (libsource (lib "") (part "WS2812B-B"))
    )
    (comp (ref "LED47")
      (value "WS2812B-B")
      (fields (field (name "Manufacturer") "worldsemi"))
      (libsource (lib "") (part "WS2812B-B"))
    )
    (comp (ref "LED48")
      (value "WS2812B-B")
      (fields (field (name "Manufacturer") "worldsemi"))
      (libsource (lib "") (part "WS2812B-B"))
    )
    (comp (ref "LED49")
      (value "WS2812B-B")
      (fields (field (name "Manufacturer") "worldsemi"))
      (libsource (lib "") (part "WS2812B-B"))
    )
    (comp (ref "LED50")
      (value "WS2812B-B")
      (fields (field (name "Manufacturer") "worldsemi"))
      (libsource (lib "") (part "WS2812B-B"))
    )
    (comp (ref "LED51")
      (value "WS2812B-B")
      (fields (field (name "Manufacturer") "worldsemi"))
      (libsource (lib "") (part "WS2812B-B"))
    )
    (comp (ref "LED52")
      (value "WS2812B-B")
      (fields (field (name "Manufacturer") "worldsemi"))
      (libsource (lib "") (part "WS2812B-B"))
    )
    (comp (ref "LED53")
      (value "WS2812B-B")
      (fields (field (name "Manufacturer") "worldsemi"))
      (libsource (lib "") (part "WS2812B-B"))
    )
    (comp (ref "LED54")
      (value "WS2812B-B")
      (fields (field (name "Manufacturer") "worldsemi"))
      (libsource (lib "") (part "WS2812B-B"))
    )
    (comp (ref "LED55")
      (value "WS2812B-B")
      (fields (field (name "Manufacturer") "worldsemi"))
      (libsource (lib "") (part "WS2812B-B"))
    )
    (comp (ref "LED56")
      (value "WS2812B-B")
      (fields (field (name "Manufacturer") "worldsemi"))
      (libsource (lib "") (part "WS2812B-B"))
    )
    (comp (ref "LED57")
      (value "WS2812B-B")
      (fields (field (name "Manufacturer") "worldsemi"))
      (libsource (lib "") (part "WS2812B-B"))
    )
    (comp (ref "LED58")
      (value "WS2812B-B")
      (fields (field (name "Manufacturer") "worldsemi"))
      (libsource (lib "") (part "WS2812B-B"))
    )
    (comp (ref "LED59")
      (value "WS2812B-B")
      (fields (field (name "Manufacturer") "worldsemi"))
      (libsource (lib "") (part "WS2812B-B"))
    )
    (comp (ref "LED60")
      (value "WS2812B-B")
      (fields (field (name "Manufacturer") "worldsemi"))
      (libsource (lib "") (part "WS2812B-B"))
    )
    (comp (ref "LED61")
      (value "WS2812B-B")
      (fields (field (name "Manufacturer") "worldsemi"))
      (libsource (lib "") (part "WS2812B-B"))
    )
    (comp (ref "LED62")
      (value "WS2812B-B")
      (fields (field (name "Manufacturer") "worldsemi"))
      (libsource (lib "") (part "WS2812B-B"))
    )
    (comp (ref "LED63")
      (value "WS2812B-B")
      (fields (field (name "Manufacturer") "worldsemi"))
      (libsource (lib "") (part "WS2812B-B"))
    )
    (comp (ref "LED64")
      (value "WS2812B-B")
      (fields (field (name "Manufacturer") "worldsemi"))
      (libsource (lib "") (part "WS2812B-B"))
    )
  )
  (nets
    (net (code "1") (name "+5V") (class "Default")
      (node (ref "C14") (pin "2") (pinfunction "2_2") (pintype "input"))
      (node (ref "C15") (pin "2") (pinfunction "2_2") (pintype "input"))
      (node (ref "C16") (pin "2") (pinfunction "2_2") (pintype "input"))
      (node (ref "C17") (pin "2") (pinfunction "2_2") (pintype "input"))
      (node (ref "C18") (pin "2") (pinfunction "2_2") (pintype "input"))
      (node (ref "C19") (pin "2") (pinfunction "2_2") (pintype "input"))
      (node (ref "C20") (pin "2") (pinfunction "2_2") (pintype "input"))
      (node (ref "C21") (pin "2") (pinfunction "2_2") (pintype "input"))
      (node (ref "C22") (pin "2") (pinfunction "2_2") (pintype "input"))
      (node (ref "C23") (pin "2") (pinfunction "2_2") (pintype "input"))
      (node (ref "C24") (pin "2") (pinfunction "2_2") (pintype "input"))
      (node (ref "C25") (pin "2") (pinfunction "2_2") (pintype "input"))
      (node (ref "C26") (pin "2") (pinfunction "2_2") (pintype "input"))
      (node (ref "C27") (pin "2") (pinfunction "2_2") (pintype "input"))
      (node (ref "C28") (pin "2") (pinfunction "2_2") (pintype "input"))
      (node (ref "C29") (pin "2") (pinfunction "2_2") (pintype "input"))
      (node (ref "C30") (pin "2") (pinfunction "2_2") (pintype "input"))
      (node (ref "C31") (pin "2") (pinfunction "2_2") (pintype "input"))
      (node (ref "C32") (pin "2") (pinfunction "2_2") (pintype "input"))
      (node (ref "C33") (pin "2") (pinfunction "2_2") (pintype "input"))
      (node (ref "C34") (pin "2") (pinfunction "2_2") (pintype "input"))
      (node (ref "C35") (pin "2") (pinfunction "2_2") (pintype "input"))
      (node (ref "C36") (pin "2") (pinfunction "2_2") (pintype "input"))
      (node (ref "C37") (pin "2") (pinfunction "2_2") (pintype "input"))
      (node (ref "C38") (pin "2") (pinfunction "2_2") (pintype "input"))
      (node (ref "C39") (pin "2") (pinfunction "2_2") (pintype "input"))
      (node (ref "C40") (pin "2") (pinfunction "2_2") (pintype "input"))
      (node (ref "C41") (pin "2") (pinfunction "2_2") (pintype "input"))
      (node (ref "C42") (pin "2") (pinfunction "2_2") (pintype "input"))
      (node (ref "C43") (pin "2") (pinfunction "2_2") (pintype "input"))
      (node (ref "C44") (pin "2") (pinfunction "2_2") (pintype "input"))
      (node (ref "C45") (pin "2") (pinfunction "2_2") (pintype "input"))
      (node (ref "C46") (pin "2") (pinfunction "2_2") (pintype "input"))
      (node (ref "C47") (pin "2") (pinfunction "2_2") (pintype "input"))
      (node (ref "C48") (pin "2") (pinfunction "2_2") (pintype "input"))
      (node (ref "C49") (pin "2") (pinfunction "2_2") (pintype "input"))
      (node (ref "C50") (pin "2") (pinfunction "2_2") (pintype "input"))
      (node (ref "C51") (pin "2") (pinfunction "2_2") (pintype "input"))
      (node (ref "C52") (pin "2") (pinfunction "2_2") (pintype "input"))
      (node (ref "C53") (pin "2") (pinfunction "2_2") (pintype "input"))
      (node (ref "C54") (pin "2") (pinfunction "2_2") (pintype "input"))
      (node (ref "C55") (pin "2") (pinfunction "2_2") (pintype "input"))
      (node (ref "C56") (pin "2") (pinfunction "2_2") (pintype "input"))
      (node (ref "C57") (pin "2") (pinfunction "2_2") (pintype "input"))
      (node (ref "C58") (pin "2") (pinfunction "2_2") (pintype "input"))
      (node (ref "C59") (pin "2") (pinfunction "2_2") (pintype "input"))
      (node (ref "C60") (pin "2") (pinfunction "2_2") (pintype "input"))
      (node (ref "C61") (pin "2") (pinfunction "2_2") (pintype "input"))
      (node (ref "C62") (pin "2") (pinfunction "2_2") (pintype "input"))
      (node (ref "C63") (pin "2") (pinfunction "2_2") (pintype "input"))
      (node (ref "C64") (pin "2") (pinfunction "2_2") (pintype "input"))
      (node (ref "C65") (pin "2") (pinfunction "2_2") (pintype "input"))
      (node (ref "C66") (pin "2") (pinfunction "2_2") (pintype "input"))
      (node (ref "C67") (pin "2") (pinfunction "2_2") (pintype "input"))
      (node (ref "C68") (pin "2") (pinfunction "2_2") (pintype "input"))
      (node (ref "C69") (pin "2") (pinfunction "2_2") (pintype "input"))
      (node (ref "C70") (pin "2") (pinfunction "2_2") (pintype "input"))
      (node (ref "C71") (pin "2") (pinfunction "2_2") (pintype "input"))
      (node (ref "C72") (pin "2") (pinfunction "2_2") (pintype "input"))
      (node (ref "C73") (pin "2") (pinfunction "2_2") (pintype "input"))
      (node (ref "C74") (pin "2") (pinfunction "2_2") (pintype "input"))
      (node (ref "C75") (pin "2") (pinfunction "2_2") (pintype "input"))
      (node (ref "C76") (pin "2") (pinfunction "2_2") (pintype "input"))
      (node (ref "C77") (pin "2") (pinfunction "2_2") (pintype "input"))
      (node (ref "LED1") (pin "1") (pinfunction "VDD_1") (pintype "unspecified"))
      (node (ref "LED10") (pin "1") (pinfunction "VDD_1") (pintype "unspecified"))
      (node (ref "LED11") (pin "1") (pinfunction "VDD_1") (pintype "unspecified"))
      (node (ref "LED12") (pin "1") (pinfunction "VDD_1") (pintype "unspecified"))
      (node (ref "LED13") (pin "1") (pinfunction "VDD_1") (pintype "unspecified"))
      (node (ref "LED14") (pin "1") (pinfunction "VDD_1") (pintype "unspecified"))
      (node (ref "LED15") (pin "1") (pinfunction "VDD_1") (pintype "unspecified"))
      (node (ref "LED16") (pin "1") (pinfunction "VDD_1") (pintype "unspecified"))
      (node (ref "LED17") (pin "1") (pinfunction "VDD_1") (pintype "unspecified"))
      (node (ref "LED18") (pin "1") (pinfunction "VDD_1") (pintype "unspecified"))
      (node (ref "LED19") (pin "1") (pinfunction "VDD_1") (pintype "unspecified"))
      (node (ref "LED2") (pin "1") (pinfunction "VDD_1") (pintype "unspecified"))
      (node (ref "LED20") (pin "1") (pinfunction "VDD_1") (pintype "unspecified"))
      (node (ref "LED21") (pin "1") (pinfunction "VDD_1") (pintype "unspecified"))
      (node (ref "LED22") (pin "1") (pinfunction "VDD_1") (pintype "unspecified"))
      (node (ref "LED23") (pin "1") (pinfunction "VDD_1") (pintype "unspecified"))
      (node (ref "LED24") (pin "1") (pinfunction "VDD_1") (pintype "unspecified"))
      (node (ref "LED25") (pin "1") (pinfunction "VDD_1") (pintype "unspecified"))
      (node (ref "LED26") (pin "1") (pinfunction "VDD_1") (pintype "unspecified"))
      (node (ref "LED27") (pin "1") (pinfunction "VDD_1") (pintype "unspecified"))
      (node (ref "LED28") (pin "1") (pinfunction "VDD_1") (pintype "unspecified"))
      (node (ref "LED29") (pin "1") (pinfunction "VDD_1") (pintype "unspecified"))
      (node (ref "LED3") (pin "1") (pinfunction "VDD_1") (pintype "unspecified"))
      (node (ref "LED30") (pin "1") (pinfunction "VDD_1") (pintype "unspecified"))
      (node (ref "LED31") (pin "1") (pinfunction "VDD_1") (pintype "unspecified"))
      (node (ref "LED32") (pin "1") (pinfunction "VDD_1") (pintype "unspecified"))
      (node (ref "LED33") (pin "1") (pinfunction "VDD_1") (pintype "unspecified"))
      (node (ref "LED34") (pin "1") (pinfunction "VDD_1") (pintype "unspecified"))
      (node (ref "LED35") (pin "1") (pinfunction "VDD_1") (pintype "unspecified"))
      (node (ref "LED36") (pin "1") (pinfunction "VDD_1") (pintype "unspecified"))
      (node (ref "LED37") (pin "1") (pinfunction "VDD_1") (pintype "unspecified"))
      (node (ref "LED38") (pin "1") (pinfunction "VDD_1") (pintype "unspecified"))
      (node (ref "LED39") (pin "1") (pinfunction "VDD_1") (pintype "unspecified"))
      (node (ref "LED4") (pin "1") (pinfunction "VDD_1") (pintype "unspecified"))
      (node (ref "LED40") (pin "1") (pinfunction "VDD_1") (pintype "unspecified"))
      (node (ref "LED41") (pin "1") (pinfunction "VDD_1") (pintype "unspecified"))
      (node (ref "LED42") (pin "1") (pinfunction "VDD_1") (pintype "unspecified"))
      (node (ref "LED43") (pin "1") (pinfunction "VDD_1") (pintype "unspecified"))
      (node (ref "LED44") (pin "1") (pinfunction "VDD_1") (pintype "unspecified"))
      (node (ref "LED45") (pin "1") (pinfunction "VDD_1") (pintype "unspecified"))
      (node (ref "LED46") (pin "1") (pinfunction "VDD_1") (pintype "unspecified"))
      (node (ref "LED47") (pin "1") (pinfunction "VDD_1") (pintype "unspecified"))
      (node (ref "LED48") (pin "1") (pinfunction "VDD_1") (pintype "unspecified"))
      (node (ref "LED49") (pin "1") (pinfunction "VDD_1") (pintype "unspecified"))
      (node (ref "LED5") (pin "1") (pinfunction "VDD_1") (pintype "unspecified"))
      (node (ref "LED50") (pin "1") (pinfunction "VDD_1") (pintype "unspecified"))
      (node (ref "LED51") (pin "1") (pinfunction "VDD_1") (pintype "unspecified"))
      (node (ref "LED52") (pin "1") (pinfunction "VDD_1") (pintype "unspecified"))
      (node (ref "LED53") (pin "1") (pinfunction "VDD_1") (pintype "unspecified"))
      (node (ref "LED54") (pin "1") (pinfunction "VDD_1") (pintype "unspecified"))
      (node (ref "LED55") (pin "1") (pinfunction "VDD_1") (pintype "unspecified"))
      (node (ref "LED56") (pin "1") (pinfunction "VDD_1") (pintype "unspecified"))
      (node (ref "LED57") (pin "1") (pinfunction "VDD_1") (pintype "unspecified"))
      (node (ref "LED58") (pin "1") (pinfunction "VDD_1") (pintype "unspecified"))
      (node (ref "LED59") (pin "1") (pinfunction "VDD_1") (pintype "unspecified"))
      (node (ref "LED6") (pin "1") (pinfunction "VDD_1") (pintype "unspecified"))
      (node (ref "LED60") (pin "1") (pinfunction "VDD_1") (pintype "unspecified"))
      (node (ref "LED61") (pin "1") (pinfunction "VDD_1") (pintype "unspecified"))
      (node (ref "LED62") (pin "1") (pinfunction "VDD_1") (pintype "unspecified"))
      (node (ref "LED63") (pin "1") (pinfunction "VDD_1") (pintype "unspecified"))
      (node (ref "LED64") (pin "1") (pinfunction "VDD_1") (pintype "unspecified"))
      (node (ref "LED7") (pin "1") (pinfunction "VDD_1") (pintype "unspecified"))
      (node (ref "LED8") (pin "1") (pinfunction "VDD_1") (pintype "unspecified"))
      (node (ref "LED9") (pin "1") (pinfunction "VDD_1") (pintype "unspecified"))
    )
    (net (code "2") (name "GND") (class "Default")
      (node (ref "C14") (pin "1") (pinfunction "1_1") (pintype "input"))
      (node (ref "C15") (pin "1") (pinfunction "1_1") (pintype "input"))
      (node (ref "C16") (pin "1") (pinfunction "1_1") (pintype "input"))
      (node (ref "C17") (pin "1") (pinfunction "1_1") (pintype "input"))
      (node (ref "C18") (pin "1") (pinfunction "1_1") (pintype "input"))
      (node (ref "C19") (pin "1") (pinfunction "1_1") (pintype "input"))
      (node (ref "C20") (pin "1") (pinfunction "1_1") (pintype "input"))
      (node (ref "C21") (pin "1") (pinfunction "1_1") (pintype "input"))
      (node (ref "C22") (pin "1") (pinfunction "1_1") (pintype "input"))
      (node (ref "C23") (pin "1") (pinfunction "1_1") (pintype "input"))
      (node (ref "C24") (pin "1") (pinfunction "1_1") (pintype "input"))
      (node (ref "C25") (pin "1") (pinfunction "1_1") (pintype "input"))
      (node (ref "C26") (pin "1") (pinfunction "1_1") (pintype "input"))
      (node (ref "C27") (pin "1") (pinfunction "1_1") (pintype "input"))
      (node (ref "C28") (pin "1") (pinfunction "1_1") (pintype "input"))
      (node (ref "C29") (pin "1") (pinfunction "1_1") (pintype "input"))
      (node (ref "C30") (pin "1") (pinfunction "1_1") (pintype "input"))
      (node (ref "C31") (pin "1") (pinfunction "1_1") (pintype "input"))
      (node (ref "C32") (pin "1") (pinfunction "1_1") (pintype "input"))
      (node (ref "C33") (pin "1") (pinfunction "1_1") (pintype "input"))
      (node (ref "C34") (pin "1") (pinfunction "1_1") (pintype "input"))
      (node (ref "C35") (pin "1") (pinfunction "1_1") (pintype "input"))
      (node (ref "C36") (pin "1") (pinfunction "1_1") (pintype "input"))
      (node (ref "C37") (pin "1") (pinfunction "1_1") (pintype "input"))
      (node (ref "C38") (pin "1") (pinfunction "1_1") (pintype "input"))
      (node (ref "C39") (pin "1") (pinfunction "1_1") (pintype "input"))
      (node (ref "C40") (pin "1") (pinfunction "1_1") (pintype "input"))
      (node (ref "C41") (pin "1") (pinfunction "1_1") (pintype "input"))
      (node (ref "C42") (pin "1") (pinfunction "1_1") (pintype "input"))
      (node (ref "C43") (pin "1") (pinfunction "1_1") (pintype "input"))
      (node (ref "C44") (pin "1") (pinfunction "1_1") (pintype "input"))
      (node (ref "C45") (pin "1") (pinfunction "1_1") (pintype "input"))
      (node (ref "C46") (pin "1") (pinfunction "1_1") (pintype "input"))
      (node (ref "C47") (pin "1") (pinfunction "1_1") (pintype "input"))
      (node (ref "C48") (pin "1") (pinfunction "1_1") (pintype "input"))
      (node (ref "C49") (pin "1") (pinfunction "1_1") (pintype "input"))
      (node (ref "C50") (pin "1") (pinfunction "1_1") (pintype "input"))
      (node (ref "C51") (pin "1") (pinfunction "1_1") (pintype "input"))
      (node (ref "C52") (pin "1") (pinfunction "1_1") (pintype "input"))
      (node (ref "C53") (pin "1") (pinfunction "1_1") (pintype "input"))
      (node (ref "C54") (pin "1") (pinfunction "1_1") (pintype "input"))
      (node (ref "C55") (pin "1") (pinfunction "1_1") (pintype "input"))
      (node (ref "C56") (pin "1") (pinfunction "1_1") (pintype "input"))
      (node (ref "C57") (pin "1") (pinfunction "1_1") (pintype "input"))
      (node (ref "C58") (pin "1") (pinfunction "1_1") (pintype "input"))
      (node (ref "C59") (pin "1") (pinfunction "1_1") (pintype "input"))
      (node (ref "C60") (pin "1") (pinfunction "1_1") (pintype "input"))
      (node (ref "C61") (pin "1") (pinfunction "1_1") (pintype "input"))
      (node (ref "C62") (pin "1") (pinfunction "1_1") (pintype "input"))
      (node (ref "C63") (pin "1") (pinfunction "1_1") (pintype "input"))
      (node (ref "C64") (pin "1") (pinfunction "1_1") (pintype "input"))
      (node (ref "C65") (pin "1") (pinfunction "1_1") (pintype "input"))
      (node (ref "C66") (pin "1") (pinfunction "1_1") (pintype "input"))
      (node (ref "C67") (pin "1") (pinfunction "1_1") (pintype "input"))
      (node (ref "C68") (pin "1") (pinfunction "1_1") (pintype "input"))
      (node (ref "C69") (pin "1") (pinfunction "1_1") (pintype "input"))
      (node (ref "C70") (pin "1") (pinfunction "1_1") (pintype "input"))
      (node (ref "C71") (pin "1") (pinfunction "1_1") (pintype "input"))
      (node (ref "C72") (pin "1") (pinfunction "1_1") (pintype "input"))
      (node (ref "C73") (pin "1") (pinfunction "1_1") (pintype "input"))
      (node (ref "C74") (pin "1") (pinfunction "1_1") (pintype "input"))
      (node (ref "C75") (pin "1") (pinfunction "1_1") (pintype "input"))
      (node (ref "C76") (pin "1") (pinfunction "1_1") (pintype "input"))
      (node (ref "C77") (pin "1") (pinfunction "1_1") (pintype "input"))
      (node (ref "LED1") (pin "3") (pinfunction "VSS_3") (pintype "unspecified"))
      (node (ref "LED10") (pin "3") (pinfunction "VSS_3") (pintype "unspecified"))
      (node (ref "LED11") (pin "3") (pinfunction "VSS_3") (pintype "unspecified"))
      (node (ref "LED12") (pin "3") (pinfunction "VSS_3") (pintype "unspecified"))
      (node (ref "LED13") (pin "3") (pinfunction "VSS_3") (pintype "unspecified"))
      (node (ref "LED14") (pin "3") (pinfunction "VSS_3") (pintype "unspecified"))
      (node (ref "LED15") (pin "3") (pinfunction "VSS_3") (pintype "unspecified"))
      (node (ref "LED16") (pin "3") (pinfunction "VSS_3") (pintype "unspecified"))
      (node (ref "LED17") (pin "3") (pinfunction "VSS_3") (pintype "unspecified"))
      (node (ref "LED18") (pin "3") (pinfunction "VSS_3") (pintype "unspecified"))
      (node (ref "LED19") (pin "3") (pinfunction "VSS_3") (pintype "unspecified"))
      (node (ref "LED2") (pin "3") (pinfunction "VSS_3") (pintype "unspecified"))
      (node (ref "LED20") (pin "3") (pinfunction "VSS_3") (pintype "unspecified"))
      (node (ref "LED21") (pin "3") (pinfunction "VSS_3") (pintype "unspecified"))
      (node (ref "LED22") (pin "3") (pinfunction "VSS_3") (pintype "unspecified"))
      (node (ref "LED23") (pin "3") (pinfunction "VSS_3") (pintype "unspecified"))
      (node (ref "LED24") (pin "3") (pinfunction "VSS_3") (pintype "unspecified"))
      (node (ref "LED25") (pin "3") (pinfunction "VSS_3") (pintype "unspecified"))
      (node (ref "LED26") (pin "3") (pinfunction "VSS_3") (pintype "unspecified"))
      (node (ref "LED27") (pin "3") (pinfunction "VSS_3") (pintype "unspecified"))
      (node (ref "LED28") (pin "3") (pinfunction "VSS_3") (pintype "unspecified"))
      (node (ref "LED29") (pin "3") (pinfunction "VSS_3") (pintype "unspecified"))
      (node (ref "LED3") (pin "3") (pinfunction "VSS_3") (pintype "unspecified"))
      (node (ref "LED30") (pin "3") (pinfunction "VSS_3") (pintype "unspecified"))
      (node (ref "LED31") (pin "3") (pinfunction "VSS_3") (pintype "unspecified"))
      (node (ref "LED32") (pin "3") (pinfunction "VSS_3") (pintype "unspecified"))
      (node (ref "LED33") (pin "3") (pinfunction "VSS_3") (pintype "unspecified"))
      (node (ref "LED34") (pin "3") (pinfunction "VSS_3") (pintype "unspecified"))
      (node (ref "LED35") (pin "3") (pinfunction "VSS_3") (pintype "unspecified"))
      (node (ref "LED36") (pin "3") (pinfunction "VSS_3") (pintype "unspecified"))
      (node (ref "LED37") (pin "3") (pinfunction "VSS_3") (pintype "unspecified"))
      (node (ref "LED38") (pin "3") (pinfunction "VSS_3") (pintype "unspecified"))
      (node (ref "LED39") (pin "3") (pinfunction "VSS_3") (pintype "unspecified"))
      (node (ref "LED4") (pin "3") (pinfunction "VSS_3") (pintype "unspecified"))
      (node (ref "LED40") (pin "3") (pinfunction "VSS_3") (pintype "unspecified"))
      (node (ref "LED41") (pin "3") (pinfunction "VSS_3") (pintype "unspecified"))
      (node (ref "LED42") (pin "3") (pinfunction "VSS_3") (pintype "unspecified"))
      (node (ref "LED43") (pin "3") (pinfunction "VSS_3") (pintype "unspecified"))
      (node (ref "LED44") (pin "3") (pinfunction "VSS_3") (pintype "unspecified"))
      (node (ref "LED45") (pin "3") (pinfunction "VSS_3") (pintype "unspecified"))
      (node (ref "LED46") (pin "3") (pinfunction "VSS_3") (pintype "unspecified"))
      (node (ref "LED47") (pin "3") (pinfunction "VSS_3") (pintype "unspecified"))
      (node (ref "LED48") (pin "3") (pinfunction "VSS_3") (pintype "unspecified"))
      (node (ref "LED49") (pin "3") (pinfunction "VSS_3") (pintype "unspecified"))
      (node (ref "LED5") (pin "3") (pinfunction "VSS_3") (pintype "unspecified"))
      (node (ref "LED50") (pin "3") (pinfunction "VSS_3") (pintype "unspecified"))
      (node (ref "LED51") (pin "3") (pinfunction "VSS_3") (pintype "unspecified"))
      (node (ref "LED52") (pin "3") (pinfunction "VSS_3") (pintype "unspecified"))
      (node (ref "LED53") (pin "3") (pinfunction "VSS_3") (pintype "unspecified"))
      (node (ref "LED54") (pin "3") (pinfunction "VSS_3") (pintype "unspecified"))
      (node (ref "LED55") (pin "3") (pinfunction "VSS_3") (pintype "unspecified"))
      (node (ref "LED56") (pin "3") (pinfunction "VSS_3") (pintype "unspecified"))
      (node (ref "LED57") (pin "3") (pinfunction "VSS_3") (pintype "unspecified"))
      (node (ref "LED58") (pin "3") (pinfunction "VSS_3") (pintype "unspecified"))
      (node (ref "LED59") (pin "3") (pinfunction "VSS_3") (pintype "unspecified"))
      (node (ref "LED6") (pin "3") (pinfunction "VSS_3") (pintype "unspecified"))
      (node (ref "LED60") (pin "3") (pinfunction "VSS_3") (pintype "unspecified"))
      (node (ref "LED61") (pin "3") (pinfunction "VSS_3") (pintype "unspecified"))
      (node (ref "LED62") (pin "3") (pinfunction "VSS_3") (pintype "unspecified"))
      (node (ref "LED63") (pin "3") (pinfunction "VSS_3") (pintype "unspecified"))
      (node (ref "LED64") (pin "3") (pinfunction "VSS_3") (pintype "unspecified"))
      (node (ref "LED7") (pin "3") (pinfunction "VSS_3") (pintype "unspecified"))
      (node (ref "LED8") (pin "3") (pinfunction "VSS_3") (pintype "unspecified"))
      (node (ref "LED9") (pin "3") (pinfunction "VSS_3") (pintype "unspecified"))
    )
    (net (code "3") (name "Key1") (class "Default")
      (node (ref "SW17") (pin "1") (pinfunction "1_1") (pintype "unspecified"))
      (node (ref "SW18") (pin "1") (pinfunction "1_1") (pintype "unspecified"))
      (node (ref "SW2") (pin "1") (pinfunction "1_1") (pintype "unspecified"))
      (node (ref "SW33") (pin "1") (pinfunction "1_1") (pintype "unspecified"))
      (node (ref "SW34") (pin "1") (pinfunction "1_1") (pintype "unspecified"))
      (node (ref "SW49") (pin "1") (pinfunction "1_1") (pintype "unspecified"))
      (node (ref "SW50") (pin "1") (pinfunction "1_1") (pintype "unspecified"))
      (node (ref "SW65") (pin "1") (pinfunction "1_1") (pintype "unspecified"))
    )
    (net (code "4") (name "Key2") (class "Default")
      (node (ref "SW16") (pin "1") (pinfunction "1_1") (pintype "unspecified"))
      (node (ref "SW19") (pin "1") (pinfunction "1_1") (pintype "unspecified"))
      (node (ref "SW3") (pin "1") (pinfunction "1_1") (pintype "unspecified"))
      (node (ref "SW32") (pin "1") (pinfunction "1_1") (pintype "unspecified"))
      (node (ref "SW35") (pin "1") (pinfunction "1_1") (pintype "unspecified"))
      (node (ref "SW48") (pin "1") (pinfunction "1_1") (pintype "unspecified"))
      (node (ref "SW51") (pin "1") (pinfunction "1_1") (pintype "unspecified"))
      (node (ref "SW64") (pin "1") (pinfunction "1_1") (pintype "unspecified"))
    )
    (net (code "5") (name "Key3") (class "Default")
      (node (ref "SW14") (pin "1") (pinfunction "1_1") (pintype "unspecified"))
      (node (ref "SW21") (pin "1") (pinfunction "1_1") (pintype "unspecified"))
      (node (ref "SW30") (pin "1") (pinfunction "1_1") (pintype "unspecified"))
      (node (ref "SW37") (pin "1") (pinfunction "1_1") (pintype "unspecified"))
      (node (ref "SW46") (pin "1") (pinfunction "1_1") (pintype "unspecified"))
      (node (ref "SW5") (pin "1") (pinfunction "1_1") (pintype "unspecified"))
      (node (ref "SW53") (pin "1") (pinfunction "1_1") (pintype "unspecified"))
      (node (ref "SW62") (pin "1") (pinfunction "1_1") (pintype "unspecified"))
    )
    (net (code "6") (name "Key4") (class "Default")
      (node (ref "SW15") (pin "1") (pinfunction "1_1") (pintype "unspecified"))
      (node (ref "SW20") (pin "1") (pinfunction "1_1") (pintype "unspecified"))
      (node (ref "SW31") (pin "1") (pinfunction "1_1") (pintype "unspecified"))
      (node (ref "SW36") (pin "1") (pinfunction "1_1") (pintype "unspecified"))
      (node (ref "SW4") (pin "1") (pinfunction "1_1") (pintype "unspecified"))
      (node (ref "SW47") (pin "1") (pinfunction "1_1") (pintype "unspecified"))
      (node (ref "SW52") (pin "1") (pinfunction "1_1") (pintype "unspecified"))
      (node (ref "SW63") (pin "1") (pinfunction "1_1") (pintype "unspecified"))
    )
    (net (code "7") (name "Key5") (class "Default")
      (node (ref "SW10") (pin "1") (pinfunction "1_1") (pintype "unspecified"))
      (node (ref "SW25") (pin "1") (pinfunction "1_1") (pintype "unspecified"))
      (node (ref "SW26") (pin "1") (pinfunction "1_1") (pintype "unspecified"))
      (node (ref "SW41") (pin "1") (pinfunction "1_1") (pintype "unspecified"))
      (node (ref "SW42") (pin "1") (pinfunction "1_1") (pintype "unspecified"))
      (node (ref "SW57") (pin "1") (pinfunction "1_1") (pintype "unspecified"))
      (node (ref "SW58") (pin "1") (pinfunction "1_1") (pintype "unspecified"))
      (node (ref "SW9") (pin "1") (pinfunction "1_1") (pintype "unspecified"))
    )
    (net (code "8") (name "Key6") (class "Default")
      (node (ref "SW11") (pin "1") (pinfunction "1_1") (pintype "unspecified"))
      (node (ref "SW24") (pin "1") (pinfunction "1_1") (pintype "unspecified"))
      (node (ref "SW27") (pin "1") (pinfunction "1_1") (pintype "unspecified"))
      (node (ref "SW40") (pin "1") (pinfunction "1_1") (pintype "unspecified"))
      (node (ref "SW43") (pin "1") (pinfunction "1_1") (pintype "unspecified"))
      (node (ref "SW56") (pin "1") (pinfunction "1_1") (pintype "unspecified"))
      (node (ref "SW59") (pin "1") (pinfunction "1_1") (pintype "unspecified"))
      (node (ref "SW8") (pin "1") (pinfunction "1_1") (pintype "unspecified"))
    )
    (net (code "9") (name "Key7") (class "Default")
      (node (ref "SW13") (pin "1") (pinfunction "1_1") (pintype "unspecified"))
      (node (ref "SW22") (pin "1") (pinfunction "1_1") (pintype "unspecified"))
      (node (ref "SW29") (pin "1") (pinfunction "1_1") (pintype "unspecified"))
      (node (ref "SW38") (pin "1") (pinfunction "1_1") (pintype "unspecified"))
      (node (ref "SW45") (pin "1") (pinfunction "1_1") (pintype "unspecified"))
      (node (ref "SW54") (pin "1") (pinfunction "1_1") (pintype "unspecified"))
      (node (ref "SW6") (pin "1") (pinfunction "1_1") (pintype "unspecified"))
      (node (ref "SW61") (pin "1") (pinfunction "1_1") (pintype "unspecified"))
    )
    (net (code "10") (name "Key8") (class "Default")
      (node (ref "SW12") (pin "1") (pinfunction "1_1") (pintype "unspecified"))
      (node (ref "SW23") (pin "1") (pinfunction "1_1") (pintype "unspecified"))
      (node (ref "SW28") (pin "1") (pinfunction "1_1") (pintype "unspecified"))
      (node (ref "SW39") (pin "1") (pinfunction "1_1") (pintype "unspecified"))
      (node (ref "SW44") (pin "1") (pinfunction "1_1") (pintype "unspecified"))
      (node (ref "SW55") (pin "1") (pinfunction "1_1") (pintype "unspecified"))
      (node (ref "SW60") (pin "1") (pinfunction "1_1") (pintype "unspecified"))
      (node (ref "SW7") (pin "1") (pinfunction "1_1") (pintype "unspecified"))
    )
    (net (code "11") (name "KeyRead1") (class "Default")
      (node (ref "D1") (pin "1") (pinfunction "K_1") (pintype "unspecified"))
      (node (ref "D2") (pin "1") (pinfunction "K_1") (pintype "unspecified"))
      (node (ref "D3") (pin "1") (pinfunction "K_1") (pintype "unspecified"))
      (node (ref "D4") (pin "1") (pinfunction "K_1") (pintype "unspecified"))
      (node (ref "D5") (pin "1") (pinfunction "K_1") (pintype "unspecified"))
      (node (ref "D6") (pin "1") (pinfunction "K_1") (pintype "unspecified"))
      (node (ref "D7") (pin "1") (pinfunction "K_1") (pintype "unspecified"))
      (node (ref "D8") (pin "1") (pinfunction "K_1") (pintype "unspecified"))
    )
    (net (code "12") (name "KeyRead2") (class "Default")
      (node (ref "D10") (pin "1") (pinfunction "K_1") (pintype "unspecified"))
      (node (ref "D11") (pin "1") (pinfunction "K_1") (pintype "unspecified"))
      (node (ref "D12") (pin "1") (pinfunction "K_1") (pintype "unspecified"))
      (node (ref "D13") (pin "1") (pinfunction "K_1") (pintype "unspecified"))
      (node (ref "D14") (pin "1") (pinfunction "K_1") (pintype "unspecified"))
      (node (ref "D15") (pin "1") (pinfunction "K_1") (pintype "unspecified"))
      (node (ref "D16") (pin "1") (pinfunction "K_1") (pintype "unspecified"))
      (node (ref "D9") (pin "1") (pinfunction "K_1") (pintype "unspecified"))
    )
    (net (code "13") (name "KeyRead3") (class "Default")
      (node (ref "D25") (pin "1") (pinfunction "K_1") (pintype "unspecified"))
      (node (ref "D26") (pin "1") (pinfunction "K_1") (pintype "unspecified"))
      (node (ref "D27") (pin "1") (pinfunction "K_1") (pintype "unspecified"))
      (node (ref "D28") (pin "1") (pinfunction "K_1") (pintype "unspecified"))
      (node (ref "D29") (pin "1") (pinfunction "K_1") (pintype "unspecified"))
      (node (ref "D30") (pin "1") (pinfunction "K_1") (pintype "unspecified"))
      (node (ref "D31") (pin "1") (pinfunction "K_1") (pintype "unspecified"))
      (node (ref "D32") (pin "1") (pinfunction "K_1") (pintype "unspecified"))
    )
    (net (code "14") (name "KeyRead4") (class "Default")
      (node (ref "D17") (pin "1") (pinfunction "K_1") (pintype "unspecified"))
      (node (ref "D18") (pin "1") (pinfunction "K_1") (pintype "unspecified"))
      (node (ref "D19") (pin "1") (pinfunction "K_1") (pintype "unspecified"))
      (node (ref "D20") (pin "1") (pinfunction "K_1") (pintype "unspecified"))
      (node (ref "D21") (pin "1") (pinfunction "K_1") (pintype "unspecified"))
      (node (ref "D22") (pin "1") (pinfunction "K_1") (pintype "unspecified"))
      (node (ref "D23") (pin "1") (pinfunction "K_1") (pintype "unspecified"))
      (node (ref "D24") (pin "1") (pinfunction "K_1") (pintype "unspecified"))
    )
    (net (code "15") (name "KeyRead5") (class "Default")
      (node (ref "D57") (pin "1") (pinfunction "K_1") (pintype "unspecified"))
      (node (ref "D58") (pin "1") (pinfunction "K_1") (pintype "unspecified"))
      (node (ref "D59") (pin "1") (pinfunction "K_1") (pintype "unspecified"))
      (node (ref "D60") (pin "1") (pinfunction "K_1") (pintype "unspecified"))
      (node (ref "D61") (pin "1") (pinfunction "K_1") (pintype "unspecified"))
      (node (ref "D62") (pin "1") (pinfunction "K_1") (pintype "unspecified"))
      (node (ref "D63") (pin "1") (pinfunction "K_1") (pintype "unspecified"))
      (node (ref "D64") (pin "1") (pinfunction "K_1") (pintype "unspecified"))
    )
    (net (code "16") (name "KeyRead6") (class "Default")
      (node (ref "D49") (pin "1") (pinfunction "K_1") (pintype "unspecified"))
      (node (ref "D50") (pin "1") (pinfunction "K_1") (pintype "unspecified"))
      (node (ref "D51") (pin "1") (pinfunction "K_1") (pintype "unspecified"))
      (node (ref "D52") (pin "1") (pinfunction "K_1") (pintype "unspecified"))
      (node (ref "D53") (pin "1") (pinfunction "K_1") (pintype "unspecified"))
      (node (ref "D54") (pin "1") (pinfunction "K_1") (pintype "unspecified"))
      (node (ref "D55") (pin "1") (pinfunction "K_1") (pintype "unspecified"))
      (node (ref "D56") (pin "1") (pinfunction "K_1") (pintype "unspecified"))
    )
    (net (code "17") (name "KeyRead7") (class "Default")
      (node (ref "D33") (pin "1") (pinfunction "K_1") (pintype "unspecified"))
      (node (ref "D34") (pin "1") (pinfunction "K_1") (pintype "unspecified"))
      (node (ref "D35") (pin "1") (pinfunction "K_1") (pintype "unspecified"))
      (node (ref "D36") (pin "1") (pinfunction "K_1") (pintype "unspecified"))
      (node (ref "D37") (pin "1") (pinfunction "K_1") (pintype "unspecified"))
      (node (ref "D38") (pin "1") (pinfunction "K_1") (pintype "unspecified"))
      (node (ref "D39") (pin "1") (pinfunction "K_1") (pintype "unspecified"))
      (node (ref "D40") (pin "1") (pinfunction "K_1") (pintype "unspecified"))
    )
    (net (code "18") (name "KeyRead8") (class "Default")
      (node (ref "D41") (pin "1") (pinfunction "K_1") (pintype "unspecified"))
      (node (ref "D42") (pin "1") (pinfunction "K_1") (pintype "unspecified"))
      (node (ref "D43") (pin "1") (pinfunction "K_1") (pintype "unspecified"))
      (node (ref "D44") (pin "1") (pinfunction "K_1") (pintype "unspecified"))
      (node (ref "D45") (pin "1") (pinfunction "K_1") (pintype "unspecified"))
      (node (ref "D46") (pin "1") (pinfunction "K_1") (pintype "unspecified"))
      (node (ref "D47") (pin "1") (pinfunction "K_1") (pintype "unspecified"))
      (node (ref "D48") (pin "1") (pinfunction "K_1") (pintype "unspecified"))
    )
    (net (code "19") (name "LEDdata") (class "Default")
      (node (ref "LED49") (pin "4") (pinfunction "DIN_4") (pintype "unspecified"))
    )
    (net (code "20") (name "LEDext") (class "Default")
      (node (ref "LED11") (pin "2") (pinfunction "DOUT_2") (pintype "unspecified"))
    )
    (net (code "21") (name "Net-(D1-A)") (class "Default")
      (node (ref "D1") (pin "2") (pinfunction "A_2") (pintype "unspecified"))
      (node (ref "SW2") (pin "2") (pinfunction "2_2") (pintype "unspecified"))
    )
    (net (code "22") (name "Net-(D2-A)") (class "Default")
      (node (ref "D2") (pin "2") (pinfunction "A_2") (pintype "unspecified"))
      (node (ref "SW3") (pin "2") (pinfunction "2_2") (pintype "unspecified"))
    )
    (net (code "23") (name "Net-(D3-A)") (class "Default")
      (node (ref "D3") (pin "2") (pinfunction "A_2") (pintype "unspecified"))
      (node (ref "SW4") (pin "2") (pinfunction "2_2") (pintype "unspecified"))
    )
    (net (code "24") (name "Net-(D4-A)") (class "Default")
      (node (ref "D4") (pin "2") (pinfunction "A_2") (pintype "unspecified"))
      (node (ref "SW5") (pin "2") (pinfunction "2_2") (pintype "unspecified"))
    )
    (net (code "25") (name "Net-(D5-A)") (class "Default")
      (node (ref "D5") (pin "2") (pinfunction "A_2") (pintype "unspecified"))
      (node (ref "SW6") (pin "2") (pinfunction "2_2") (pintype "unspecified"))
    )
    (net (code "26") (name "Net-(D6-A)") (class "Default")
      (node (ref "D6") (pin "2") (pinfunction "A_2") (pintype "unspecified"))
      (node (ref "SW7") (pin "2") (pinfunction "2_2") (pintype "unspecified"))
    )
    (net (code "27") (name "Net-(D7-A)") (class "Default")
      (node (ref "D7") (pin "2") (pinfunction "A_2") (pintype "unspecified"))
      (node (ref "SW8") (pin "2") (pinfunction "2_2") (pintype "unspecified"))
    )
    (net (code "28") (name "Net-(D8-A)") (class "Default")
      (node (ref "D8") (pin "2") (pinfunction "A_2") (pintype "unspecified"))
      (node (ref "SW9") (pin "2") (pinfunction "2_2") (pintype "unspecified"))
    )
    (net (code "29") (name "Net-(D9-A)") (class "Default")
      (node (ref "D9") (pin "2") (pinfunction "A_2") (pintype "unspecified"))
      (node (ref "SW10") (pin "2") (pinfunction "2_2") (pintype "unspecified"))
    )
    (net (code "30") (name "Net-(D10-A)") (class "Default")
      (node (ref "D10") (pin "2") (pinfunction "A_2") (pintype "unspecified"))
      (node (ref "SW11") (pin "2") (pinfunction "2_2") (pintype "unspecified"))
    )
    (net (code "31") (name "Net-(D11-A)") (class "Default")
      (node (ref "D11") (pin "2") (pinfunction "A_2") (pintype "unspecified"))
      (node (ref "SW13") (pin "2") (pinfunction "2_2") (pintype "unspecified"))
    )
    (net (code "32") (name "Net-(D12-A)") (class "Default")
      (node (ref "D12") (pin "2") (pinfunction "A_2") (pintype "unspecified"))
      (node (ref "SW14") (pin "2") (pinfunction "2_2") (pintype "unspecified"))
    )
    (net (code "33") (name "Net-(D13-A)") (class "Default")
      (node (ref "D13") (pin "2") (pinfunction "A_2") (pintype "unspecified"))
      (node (ref "SW15") (pin "2") (pinfunction "2_2") (pintype "unspecified"))
    )
    (net (code "34") (name "Net-(D14-A)") (class "Default")
      (node (ref "D14") (pin "2") (pinfunction "A_2") (pintype "unspecified"))
      (node (ref "SW16") (pin "2") (pinfunction "2_2") (pintype "unspecified"))
    )
    (net (code "35") (name "Net-(D15-A)") (class "Default")
      (node (ref "D15") (pin "2") (pinfunction "A_2") (pintype "unspecified"))
      (node (ref "SW17") (pin "2") (pinfunction "2_2") (pintype "unspecified"))
    )
    (net (code "36") (name "Net-(D16-A)") (class "Default")
      (node (ref "D16") (pin "2") (pinfunction "A_2") (pintype "unspecified"))
      (node (ref "SW12") (pin "2") (pinfunction "2_2") (pintype "unspecified"))
    )
    (net (code "37") (name "Net-(D17-A)") (class "Default")
      (node (ref "D17") (pin "2") (pinfunction "A_2") (pintype "unspecified"))
      (node (ref "SW23") (pin "2") (pinfunction "2_2") (pintype "unspecified"))
    )
    (net (code "38") (name "Net-(D18-A)") (class "Default")
      (node (ref "D18") (pin "2") (pinfunction "A_2") (pintype "unspecified"))
      (node (ref "SW18") (pin "2") (pinfunction "2_2") (pintype "unspecified"))
    )
    (net (code "39") (name "Net-(D19-A)") (class "Default")
      (node (ref "D19") (pin "2") (pinfunction "A_2") (pintype "unspecified"))
      (node (ref "SW19") (pin "2") (pinfunction "2_2") (pintype "unspecified"))
    )
    (net (code "40") (name "Net-(D20-A)") (class "Default")
      (node (ref "D20") (pin "2") (pinfunction "A_2") (pintype "unspecified"))
      (node (ref "SW20") (pin "2") (pinfunction "2_2") (pintype "unspecified"))
    )
    (net (code "41") (name "Net-(D21-A)") (class "Default")
      (node (ref "D21") (pin "2") (pinfunction "A_2") (pintype "unspecified"))
      (node (ref "SW21") (pin "2") (pinfunction "2_2") (pintype "unspecified"))
    )
    (net (code "42") (name "Net-(D22-A)") (class "Default")
      (node (ref "D22") (pin "2") (pinfunction "A_2") (pintype "unspecified"))
      (node (ref "SW22") (pin "2") (pinfunction "2_2") (pintype "unspecified"))
    )
    (net (code "43") (name "Net-(D23-A)") (class "Default")
      (node (ref "D23") (pin "2") (pinfunction "A_2") (pintype "unspecified"))
      (node (ref "SW24") (pin "2") (pinfunction "2_2") (pintype "unspecified"))
    )
    (net (code "44") (name "Net-(D24-A)") (class "Default")
      (node (ref "D24") (pin "2") (pinfunction "A_2") (pintype "unspecified"))
      (node (ref "SW25") (pin "2") (pinfunction "2_2") (pintype "unspecified"))
    )
    (net (code "45") (name "Net-(D25-A)") (class "Default")
      (node (ref "D25") (pin "2") (pinfunction "A_2") (pintype "unspecified"))
      (node (ref "SW26") (pin "2") (pinfunction "2_2") (pintype "unspecified"))
    )
    (net (code "46") (name "Net-(D26-A)") (class "Default")
      (node (ref "D26") (pin "2") (pinfunction "A_2") (pintype "unspecified"))
      (node (ref "SW27") (pin "2") (pinfunction "2_2") (pintype "unspecified"))
    )
    (net (code "47") (name "Net-(D27-A)") (class "Default")
      (node (ref "D27") (pin "2") (pinfunction "A_2") (pintype "unspecified"))
      (node (ref "SW28") (pin "2") (pinfunction "2_2") (pintype "unspecified"))
    )
    (net (code "48") (name "Net-(D28-A)") (class "Default")
      (node (ref "D28") (pin "2") (pinfunction "A_2") (pintype "unspecified"))
      (node (ref "SW29") (pin "2") (pinfunction "2_2") (pintype "unspecified"))
    )
    (net (code "49") (name "Net-(D29-A)") (class "Default")
      (node (ref "D29") (pin "2") (pinfunction "A_2") (pintype "unspecified"))
      (node (ref "SW30") (pin "2") (pinfunction "2_2") (pintype "unspecified"))
    )
    (net (code "50") (name "Net-(D30-A)") (class "Default")
      (node (ref "D30") (pin "2") (pinfunction "A_2") (pintype "unspecified"))
      (node (ref "SW31") (pin "2") (pinfunction "2_2") (pintype "unspecified"))
    )
    (net (code "51") (name "Net-(D31-A)") (class "Default")
      (node (ref "D31") (pin "2") (pinfunction "A_2") (pintype "unspecified"))
      (node (ref "SW32") (pin "2") (pinfunction "2_2") (pintype "unspecified"))
    )
    (net (code "52") (name "Net-(D32-A)") (class "Default")
      (node (ref "D32") (pin "2") (pinfunction "A_2") (pintype "unspecified"))
      (node (ref "SW33") (pin "2") (pinfunction "2_2") (pintype "unspecified"))
    )
    (net (code "53") (name "Net-(D33-A)") (class "Default")
      (node (ref "D33") (pin "2") (pinfunction "A_2") (pintype "unspecified"))
      (node (ref "SW34") (pin "2") (pinfunction "2_2") (pintype "unspecified"))
    )
    (net (code "54") (name "Net-(D34-A)") (class "Default")
      (node (ref "D34") (pin "2") (pinfunction "A_2") (pintype "unspecified"))
      (node (ref "SW35") (pin "2") (pinfunction "2_2") (pintype "unspecified"))
    )
    (net (code "55") (name "Net-(D35-A)") (class "Default")
      (node (ref "D35") (pin "2") (pinfunction "A_2") (pintype "unspecified"))
      (node (ref "SW36") (pin "2") (pinfunction "2_2") (pintype "unspecified"))
    )
    (net (code "56") (name "Net-(D36-A)") (class "Default")
      (node (ref "D36") (pin "2") (pinfunction "A_2") (pintype "unspecified"))
      (node (ref "SW37") (pin "2") (pinfunction "2_2") (pintype "unspecified"))
    )
    (net (code "57") (name "Net-(D37-A)") (class "Default")
      (node (ref "D37") (pin "2") (pinfunction "A_2") (pintype "unspecified"))
      (node (ref "SW38") (pin "2") (pinfunction "2_2") (pintype "unspecified"))
    )
    (net (code "58") (name "Net-(D38-A)") (class "Default")
      (node (ref "D38") (pin "2") (pinfunction "A_2") (pintype "unspecified"))
      (node (ref "SW39") (pin "2") (pinfunction "2_2") (pintype "unspecified"))
    )
    (net (code "59") (name "Net-(D39-A)") (class "Default")
      (node (ref "D39") (pin "2") (pinfunction "A_2") (pintype "unspecified"))
      (node (ref "SW40") (pin "2") (pinfunction "2_2") (pintype "unspecified"))
    )
    (net (code "60") (name "Net-(D40-A)") (class "Default")
      (node (ref "D40") (pin "2") (pinfunction "A_2") (pintype "unspecified"))
      (node (ref "SW41") (pin "2") (pinfunction "2_2") (pintype "unspecified"))
    )
    (net (code "61") (name "Net-(D41-A)") (class "Default")
      (node (ref "D41") (pin "2") (pinfunction "A_2") (pintype "unspecified"))
      (node (ref "SW42") (pin "2") (pinfunction "2_2") (pintype "unspecified"))
    )
    (net (code "62") (name "Net-(D42-A)") (class "Default")
      (node (ref "D42") (pin "2") (pinfunction "A_2") (pintype "unspecified"))
      (node (ref "SW43") (pin "2") (pinfunction "2_2") (pintype "unspecified"))
    )
    (net (code "63") (name "Net-(D43-A)") (class "Default")
      (node (ref "D43") (pin "2") (pinfunction "A_2") (pintype "unspecified"))
      (node (ref "SW45") (pin "2") (pinfunction "2_2") (pintype "unspecified"))
    )
    (net (code "64") (name "Net-(D44-A)") (class "Default")
      (node (ref "D44") (pin "2") (pinfunction "A_2") (pintype "unspecified"))
      (node (ref "SW46") (pin "2") (pinfunction "2_2") (pintype "unspecified"))
    )
    (net (code "65") (name "Net-(D45-A)") (class "Default")
      (node (ref "D45") (pin "2") (pinfunction "A_2") (pintype "unspecified"))
      (node (ref "SW47") (pin "2") (pinfunction "2_2") (pintype "unspecified"))
    )
    (net (code "66") (name "Net-(D46-A)") (class "Default")
      (node (ref "D46") (pin "2") (pinfunction "A_2") (pintype "unspecified"))
      (node (ref "SW48") (pin "2") (pinfunction "2_2") (pintype "unspecified"))
    )
    (net (code "67") (name "Net-(D47-A)") (class "Default")
      (node (ref "D47") (pin "2") (pinfunction "A_2") (pintype "unspecified"))
      (node (ref "SW49") (pin "2") (pinfunction "2_2") (pintype "unspecified"))
    )
    (net (code "68") (name "Net-(D48-A)") (class "Default")
      (node (ref "D48") (pin "2") (pinfunction "A_2") (pintype "unspecified"))
      (node (ref "SW44") (pin "2") (pinfunction "2_2") (pintype "unspecified"))
    )
    (net (code "69") (name "Net-(D49-A)") (class "Default")
      (node (ref "D49") (pin "2") (pinfunction "A_2") (pintype "unspecified"))
      (node (ref "SW55") (pin "2") (pinfunction "2_2") (pintype "unspecified"))
    )
    (net (code "70") (name "Net-(D50-A)") (class "Default")
      (node (ref "D50") (pin "2") (pinfunction "A_2") (pintype "unspecified"))
      (node (ref "SW50") (pin "2") (pinfunction "2_2") (pintype "unspecified"))
    )
    (net (code "71") (name "Net-(D51-A)") (class "Default")
      (node (ref "D51") (pin "2") (pinfunction "A_2") (pintype "unspecified"))
      (node (ref "SW51") (pin "2") (pinfunction "2_2") (pintype "unspecified"))
    )
    (net (code "72") (name "Net-(D52-A)") (class "Default")
      (node (ref "D52") (pin "2") (pinfunction "A_2") (pintype "unspecified"))
      (node (ref "SW52") (pin "2") (pinfunction "2_2") (pintype "unspecified"))
    )
    (net (code "73") (name "Net-(D53-A)") (class "Default")
      (node (ref "D53") (pin "2") (pinfunction "A_2") (pintype "unspecified"))
      (node (ref "SW53") (pin "2") (pinfunction "2_2") (pintype "unspecified"))
    )
    (net (code "74") (name "Net-(D54-A)") (class "Default")
      (node (ref "D54") (pin "2") (pinfunction "A_2") (pintype "unspecified"))
      (node (ref "SW54") (pin "2") (pinfunction "2_2") (pintype "unspecified"))
    )
    (net (code "75") (name "Net-(D55-A)") (class "Default")
      (node (ref "D55") (pin "2") (pinfunction "A_2") (pintype "unspecified"))
      (node (ref "SW56") (pin "2") (pinfunction "2_2") (pintype "unspecified"))
    )
    (net (code "76") (name "Net-(D56-A)") (class "Default")
      (node (ref "D56") (pin "2") (pinfunction "A_2") (pintype "unspecified"))
      (node (ref "SW57") (pin "2") (pinfunction "2_2") (pintype "unspecified"))
    )
    (net (code "77") (name "Net-(D57-A)") (class "Default")
      (node (ref "D57") (pin "2") (pinfunction "A_2") (pintype "unspecified"))
      (node (ref "SW58") (pin "2") (pinfunction "2_2") (pintype "unspecified"))
    )
    (net (code "78") (name "Net-(D58-A)") (class "Default")
      (node (ref "D58") (pin "2") (pinfunction "A_2") (pintype "unspecified"))
      (node (ref "SW59") (pin "2") (pinfunction "2_2") (pintype "unspecified"))
    )
    (net (code "79") (name "Net-(D59-A)") (class "Default")
      (node (ref "D59") (pin "2") (pinfunction "A_2") (pintype "unspecified"))
      (node (ref "SW60") (pin "2") (pinfunction "2_2") (pintype "unspecified"))
    )
    (net (code "80") (name "Net-(D60-A)") (class "Default")
      (node (ref "D60") (pin "2") (pinfunction "A_2") (pintype "unspecified"))
      (node (ref "SW61") (pin "2") (pinfunction "2_2") (pintype "unspecified"))
    )
    (net (code "81") (name "Net-(D61-A)") (class "Default")
      (node (ref "D61") (pin "2") (pinfunction "A_2") (pintype "unspecified"))
      (node (ref "SW62") (pin "2") (pinfunction "2_2") (pintype "unspecified"))
    )
    (net (code "82") (name "Net-(D62-A)") (class "Default")
      (node (ref "D62") (pin "2") (pinfunction "A_2") (pintype "unspecified"))
      (node (ref "SW63") (pin "2") (pinfunction "2_2") (pintype "unspecified"))
    )
    (net (code "83") (name "Net-(D63-A)") (class "Default")
      (node (ref "D63") (pin "2") (pinfunction "A_2") (pintype "unspecified"))
      (node (ref "SW64") (pin "2") (pinfunction "2_2") (pintype "unspecified"))
    )
    (net (code "84") (name "Net-(D64-A)") (class "Default")
      (node (ref "D64") (pin "2") (pinfunction "A_2") (pintype "unspecified"))
      (node (ref "SW65") (pin "2") (pinfunction "2_2") (pintype "unspecified"))
    )
    (net (code "85") (name "Net-(LED1-DIN)") (class "Default")
      (node (ref "LED1") (pin "4") (pinfunction "DIN_4") (pintype "unspecified"))
      (node (ref "LED22") (pin "2") (pinfunction "DOUT_2") (pintype "unspecified"))
    )
    (net (code "86") (name "Net-(LED1-DOUT)") (class "Default")
      (node (ref "LED1") (pin "2") (pinfunction "DOUT_2") (pintype "unspecified"))
      (node (ref "LED2") (pin "4") (pinfunction "DIN_4") (pintype "unspecified"))
    )
    (net (code "87") (name "Net-(LED2-DOUT)") (class "Default")
      (node (ref "LED2") (pin "2") (pinfunction "DOUT_2") (pintype "unspecified"))
      (node (ref "LED4") (pin "4") (pinfunction "DIN_4") (pintype "unspecified"))
    )
    (net (code "88") (name "Net-(LED3-DIN)") (class "Default")
      (node (ref "LED3") (pin "4") (pinfunction "DIN_4") (pintype "unspecified"))
      (node (ref "LED4") (pin "2") (pinfunction "DOUT_2") (pintype "unspecified"))
    )
    (net (code "89") (name "Net-(LED3-DOUT)") (class "Default")
      (node (ref "LED3") (pin "2") (pinfunction "DOUT_2") (pintype "unspecified"))
      (node (ref "LED8") (pin "4") (pinfunction "DIN_4") (pintype "unspecified"))
    )
    (net (code "90") (name "Net-(LED5-DIN)") (class "Default")
      (node (ref "LED5") (pin "4") (pinfunction "DIN_4") (pintype "unspecified"))
      (node (ref "LED7") (pin "2") (pinfunction "DOUT_2") (pintype "unspecified"))
    )
    (net (code "91") (name "Net-(LED5-DOUT)") (class "Default")
      (node (ref "LED5") (pin "2") (pinfunction "DOUT_2") (pintype "unspecified"))
      (node (ref "LED6") (pin "4") (pinfunction "DIN_4") (pintype "unspecified"))
    )
    (net (code "92") (name "Net-(LED7-DIN)") (class "Default")
      (node (ref "LED7") (pin "4") (pinfunction "DIN_4") (pintype "unspecified"))
      (node (ref "LED8") (pin "2") (pinfunction "DOUT_2") (pintype "unspecified"))
    )
    (net (code "93") (name "Net-(LED10-DIN)") (class "Default")
      (node (ref "LED10") (pin "4") (pinfunction "DIN_4") (pintype "unspecified"))
      (node (ref "LED9") (pin "2") (pinfunction "DOUT_2") (pintype "unspecified"))
    )
    (net (code "94") (name "Net-(LED10-DOUT)") (class "Default")
      (node (ref "LED10") (pin "2") (pinfunction "DOUT_2") (pintype "unspecified"))
      (node (ref "LED12") (pin "4") (pinfunction "DIN_4") (pintype "unspecified"))
    )
    (net (code "95") (name "Net-(LED11-DIN)") (class "Default")
      (node (ref "LED11") (pin "4") (pinfunction "DIN_4") (pintype "unspecified"))
      (node (ref "LED12") (pin "2") (pinfunction "DOUT_2") (pintype "unspecified"))
    )
    (net (code "96") (name "Net-(LED13-DIN)") (class "Default")
      (node (ref "LED13") (pin "4") (pinfunction "DIN_4") (pintype "unspecified"))
      (node (ref "LED15") (pin "2") (pinfunction "DOUT_2") (pintype "unspecified"))
    )
    (net (code "97") (name "Net-(LED13-DOUT)") (class "Default")
      (node (ref "LED13") (pin "2") (pinfunction "DOUT_2") (pintype "unspecified"))
      (node (ref "LED14") (pin "4") (pinfunction "DIN_4") (pintype "unspecified"))
    )
    (net (code "98") (name "Net-(LED14-DOUT)") (class "Default")
      (node (ref "LED14") (pin "2") (pinfunction "DOUT_2") (pintype "unspecified"))
      (node (ref "LED9") (pin "4") (pinfunction "DIN_4") (pintype "unspecified"))
    )
    (net (code "99") (name "Net-(LED15-DIN)") (class "Default")
      (node (ref "LED15") (pin "4") (pinfunction "DIN_4") (pintype "unspecified"))
      (node (ref "LED16") (pin "2") (pinfunction "DOUT_2") (pintype "unspecified"))
    )
    (net (code "100") (name "Net-(LED16-DIN)") (class "Default")
      (node (ref "LED16") (pin "4") (pinfunction "DIN_4") (pintype "unspecified"))
      (node (ref "LED6") (pin "2") (pinfunction "DOUT_2") (pintype "unspecified"))
    )
    (net (code "101") (name "Net-(LED17-DIN)") (class "Default")
      (node (ref "LED17") (pin "4") (pinfunction "DIN_4") (pintype "unspecified"))
      (node (ref "LED27") (pin "2") (pinfunction "DOUT_2") (pintype "unspecified"))
    )
    (net (code "102") (name "Net-(LED17-DOUT)") (class "Default")
      (node (ref "LED17") (pin "2") (pinfunction "DOUT_2") (pintype "unspecified"))
      (node (ref "LED18") (pin "4") (pinfunction "DIN_4") (pintype "unspecified"))
    )
    (net (code "103") (name "Net-(LED18-DOUT)") (class "Default")
      (node (ref "LED18") (pin "2") (pinfunction "DOUT_2") (pintype "unspecified"))
      (node (ref "LED20") (pin "4") (pinfunction "DIN_4") (pintype "unspecified"))
    )
    (net (code "104") (name "Net-(LED19-DIN)") (class "Default")
      (node (ref "LED19") (pin "4") (pinfunction "DIN_4") (pintype "unspecified"))
      (node (ref "LED20") (pin "2") (pinfunction "DOUT_2") (pintype "unspecified"))
    )
    (net (code "105") (name "Net-(LED19-DOUT)") (class "Default")
      (node (ref "LED19") (pin "2") (pinfunction "DOUT_2") (pintype "unspecified"))
      (node (ref "LED24") (pin "4") (pinfunction "DIN_4") (pintype "unspecified"))
    )
    (net (code "106") (name "Net-(LED21-DIN)") (class "Default")
      (node (ref "LED21") (pin "4") (pinfunction "DIN_4") (pintype "unspecified"))
      (node (ref "LED23") (pin "2") (pinfunction "DOUT_2") (pintype "unspecified"))
    )
    (net (code "107") (name "Net-(LED21-DOUT)") (class "Default")
      (node (ref "LED21") (pin "2") (pinfunction "DOUT_2") (pintype "unspecified"))
      (node (ref "LED22") (pin "4") (pinfunction "DIN_4") (pintype "unspecified"))
    )
    (net (code "108") (name "Net-(LED23-DIN)") (class "Default")
      (node (ref "LED23") (pin "4") (pinfunction "DIN_4") (pintype "unspecified"))
      (node (ref "LED24") (pin "2") (pinfunction "DOUT_2") (pintype "unspecified"))
    )
    (net (code "109") (name "Net-(LED25-DIN)") (class "Default")
      (node (ref "LED25") (pin "4") (pinfunction "DIN_4") (pintype "unspecified"))
      (node (ref "LED30") (pin "2") (pinfunction "DOUT_2") (pintype "unspecified"))
    )
    (net (code "110") (name "Net-(LED25-DOUT)") (class "Default")
      (node (ref "LED25") (pin "2") (pinfunction "DOUT_2") (pintype "unspecified"))
      (node (ref "LED26") (pin "4") (pinfunction "DIN_4") (pintype "unspecified"))
    )
    (net (code "111") (name "Net-(LED26-DOUT)") (class "Default")
      (node (ref "LED26") (pin "2") (pinfunction "DOUT_2") (pintype "unspecified"))
      (node (ref "LED28") (pin "4") (pinfunction "DIN_4") (pintype "unspecified"))
    )
    (net (code "112") (name "Net-(LED27-DIN)") (class "Default")
      (node (ref "LED27") (pin "4") (pinfunction "DIN_4") (pintype "unspecified"))
      (node (ref "LED28") (pin "2") (pinfunction "DOUT_2") (pintype "unspecified"))
    )
    (net (code "113") (name "Net-(LED29-DIN)") (class "Default")
      (node (ref "LED29") (pin "4") (pinfunction "DIN_4") (pintype "unspecified"))
      (node (ref "LED31") (pin "2") (pinfunction "DOUT_2") (pintype "unspecified"))
    )
    (net (code "114") (name "Net-(LED29-DOUT)") (class "Default")
      (node (ref "LED29") (pin "2") (pinfunction "DOUT_2") (pintype "unspecified"))
      (node (ref "LED30") (pin "4") (pinfunction "DIN_4") (pintype "unspecified"))
    )
    (net (code "115") (name "Net-(LED31-DIN)") (class "Default")
      (node (ref "LED31") (pin "4") (pinfunction "DIN_4") (pintype "unspecified"))
      (node (ref "LED32") (pin "2") (pinfunction "DOUT_2") (pintype "unspecified"))
    )
    (net (code "116") (name "Net-(LED32-DIN)") (class "Default")
      (node (ref "LED32") (pin "4") (pinfunction "DIN_4") (pintype "unspecified"))
      (node (ref "LED43") (pin "2") (pinfunction "DOUT_2") (pintype "unspecified"))
    )
    (net (code "117") (name "Net-(LED33-DIN)") (class "Default")
      (node (ref "LED33") (pin "4") (pinfunction "DIN_4") (pintype "unspecified"))
      (node (ref "LED59") (pin "2") (pinfunction "DOUT_2") (pintype "unspecified"))
    )
    (net (code "118") (name "Net-(LED33-DOUT)") (class "Default")
      (node (ref "LED33") (pin "2") (pinfunction "DOUT_2") (pintype "unspecified"))
      (node (ref "LED34") (pin "4") (pinfunction "DIN_4") (pintype "unspecified"))
    )
    (net (code "119") (name "Net-(LED34-DOUT)") (class "Default")
      (node (ref "LED34") (pin "2") (pinfunction "DOUT_2") (pintype "unspecified"))
      (node (ref "LED36") (pin "4") (pinfunction "DIN_4") (pintype "unspecified"))
    )
    (net (code "120") (name "Net-(LED35-DIN)") (class "Default")
      (node (ref "LED35") (pin "4") (pinfunction "DIN_4") (pintype "unspecified"))
      (node (ref "LED36") (pin "2") (pinfunction "DOUT_2") (pintype "unspecified"))
    )
    (net (code "121") (name "Net-(LED35-DOUT)") (class "Default")
      (node (ref "LED35") (pin "2") (pinfunction "DOUT_2") (pintype "unspecified"))
      (node (ref "LED40") (pin "4") (pinfunction "DIN_4") (pintype "unspecified"))
    )
    (net (code "122") (name "Net-(LED37-DIN)") (class "Default")
      (node (ref "LED37") (pin "4") (pinfunction "DIN_4") (pintype "unspecified"))
      (node (ref "LED39") (pin "2") (pinfunction "DOUT_2") (pintype "unspecified"))
    )
    (net (code "123") (name "Net-(LED37-DOUT)") (class "Default")
      (node (ref "LED37") (pin "2") (pinfunction "DOUT_2") (pintype "unspecified"))
      (node (ref "LED38") (pin "4") (pinfunction "DIN_4") (pintype "unspecified"))
    )
    (net (code "124") (name "Net-(LED38-DOUT)") (class "Default")
      (node (ref "LED38") (pin "2") (pinfunction "DOUT_2") (pintype "unspecified"))
      (node (ref "LED48") (pin "4") (pinfunction "DIN_4") (pintype "unspecified"))
    )
    (net (code "125") (name "Net-(LED39-DIN)") (class "Default")
      (node (ref "LED39") (pin "4") (pinfunction "DIN_4") (pintype "unspecified"))
      (node (ref "LED40") (pin "2") (pinfunction "DOUT_2") (pintype "unspecified"))
    )
    (net (code "126") (name "Net-(LED41-DIN)") (class "Default")
      (node (ref "LED41") (pin "4") (pinfunction "DIN_4") (pintype "unspecified"))
      (node (ref "LED46") (pin "2") (pinfunction "DOUT_2") (pintype "unspecified"))
    )
    (net (code "127") (name "Net-(LED41-DOUT)") (class "Default")
      (node (ref "LED41") (pin "2") (pinfunction "DOUT_2") (pintype "unspecified"))
      (node (ref "LED42") (pin "4") (pinfunction "DIN_4") (pintype "unspecified"))
    )
    (net (code "128") (name "Net-(LED42-DOUT)") (class "Default")
      (node (ref "LED42") (pin "2") (pinfunction "DOUT_2") (pintype "unspecified"))
      (node (ref "LED44") (pin "4") (pinfunction "DIN_4") (pintype "unspecified"))
    )
    (net (code "129") (name "Net-(LED43-DIN)") (class "Default")
      (node (ref "LED43") (pin "4") (pinfunction "DIN_4") (pintype "unspecified"))
      (node (ref "LED44") (pin "2") (pinfunction "DOUT_2") (pintype "unspecified"))
    )
    (net (code "130") (name "Net-(LED45-DIN)") (class "Default")
      (node (ref "LED45") (pin "4") (pinfunction "DIN_4") (pintype "unspecified"))
      (node (ref "LED47") (pin "2") (pinfunction "DOUT_2") (pintype "unspecified"))
    )
    (net (code "131") (name "Net-(LED45-DOUT)") (class "Default")
      (node (ref "LED45") (pin "2") (pinfunction "DOUT_2") (pintype "unspecified"))
      (node (ref "LED46") (pin "4") (pinfunction "DIN_4") (pintype "unspecified"))
    )
    (net (code "132") (name "Net-(LED47-DIN)") (class "Default")
      (node (ref "LED47") (pin "4") (pinfunction "DIN_4") (pintype "unspecified"))
      (node (ref "LED48") (pin "2") (pinfunction "DOUT_2") (pintype "unspecified"))
    )
    (net (code "133") (name "Net-(LED49-DOUT)") (class "Default")
      (node (ref "LED49") (pin "2") (pinfunction "DOUT_2") (pintype "unspecified"))
      (node (ref "LED50") (pin "4") (pinfunction "DIN_4") (pintype "unspecified"))
    )
    (net (code "134") (name "Net-(LED50-DOUT)") (class "Default")
      (node (ref "LED50") (pin "2") (pinfunction "DOUT_2") (pintype "unspecified"))
      (node (ref "LED52") (pin "4") (pinfunction "DIN_4") (pintype "unspecified"))
    )
    (net (code "135") (name "Net-(LED51-DIN)") (class "Default")
      (node (ref "LED51") (pin "4") (pinfunction "DIN_4") (pintype "unspecified"))
      (node (ref "LED52") (pin "2") (pinfunction "DOUT_2") (pintype "unspecified"))
    )
    (net (code "136") (name "Net-(LED51-DOUT)") (class "Default")
      (node (ref "LED51") (pin "2") (pinfunction "DOUT_2") (pintype "unspecified"))
      (node (ref "LED56") (pin "4") (pinfunction "DIN_4") (pintype "unspecified"))
    )
    (net (code "137") (name "Net-(LED53-DIN)") (class "Default")
      (node (ref "LED53") (pin "4") (pinfunction "DIN_4") (pintype "unspecified"))
      (node (ref "LED55") (pin "2") (pinfunction "DOUT_2") (pintype "unspecified"))
    )
    (net (code "138") (name "Net-(LED53-DOUT)") (class "Default")
      (node (ref "LED53") (pin "2") (pinfunction "DOUT_2") (pintype "unspecified"))
      (node (ref "LED54") (pin "4") (pinfunction "DIN_4") (pintype "unspecified"))
    )
    (net (code "139") (name "Net-(LED54-DOUT)") (class "Default")
      (node (ref "LED54") (pin "2") (pinfunction "DOUT_2") (pintype "unspecified"))
      (node (ref "LED64") (pin "4") (pinfunction "DIN_4") (pintype "unspecified"))
    )
    (net (code "140") (name "Net-(LED55-DIN)") (class "Default")
      (node (ref "LED55") (pin "4") (pinfunction "DIN_4") (pintype "unspecified"))
      (node (ref "LED56") (pin "2") (pinfunction "DOUT_2") (pintype "unspecified"))
    )
    (net (code "141") (name "Net-(LED57-DIN)") (class "Default")
      (node (ref "LED57") (pin "4") (pinfunction "DIN_4") (pintype "unspecified"))
      (node (ref "LED62") (pin "2") (pinfunction "DOUT_2") (pintype "unspecified"))
    )
    (net (code "142") (name "Net-(LED57-DOUT)") (class "Default")
      (node (ref "LED57") (pin "2") (pinfunction "DOUT_2") (pintype "unspecified"))
      (node (ref "LED58") (pin "4") (pinfunction "DIN_4") (pintype "unspecified"))
    )
    (net (code "143") (name "Net-(LED58-DOUT)") (class "Default")
      (node (ref "LED58") (pin "2") (pinfunction "DOUT_2") (pintype "unspecified"))
      (node (ref "LED60") (pin "4") (pinfunction "DIN_4") (pintype "unspecified"))
    )
    (net (code "144") (name "Net-(LED59-DIN)") (class "Default")
      (node (ref "LED59") (pin "4") (pinfunction "DIN_4") (pintype "unspecified"))
      (node (ref "LED60") (pin "2") (pinfunction "DOUT_2") (pintype "unspecified"))
    )
    (net (code "145") (name "Net-(LED61-DIN)") (class "Default")
      (node (ref "LED61") (pin "4") (pinfunction "DIN_4") (pintype "unspecified"))
      (node (ref "LED63") (pin "2") (pinfunction "DOUT_2") (pintype "unspecified"))
    )
    (net (code "146") (name "Net-(LED61-DOUT)") (class "Default")
      (node (ref "LED61") (pin "2") (pinfunction "DOUT_2") (pintype "unspecified"))
      (node (ref "LED62") (pin "4") (pinfunction "DIN_4") (pintype "unspecified"))
    )
    (net (code "147") (name "Net-(LED63-DIN)") (class "Default")
      (node (ref "LED63") (pin "4") (pinfunction "DIN_4") (pintype "unspecified"))
      (node (ref "LED64") (pin "2") (pinfunction "DOUT_2") (pintype "unspecified"))
    )
  )
)
